# design.net
KiCad netlist of a schematic drawn in Altium Designer
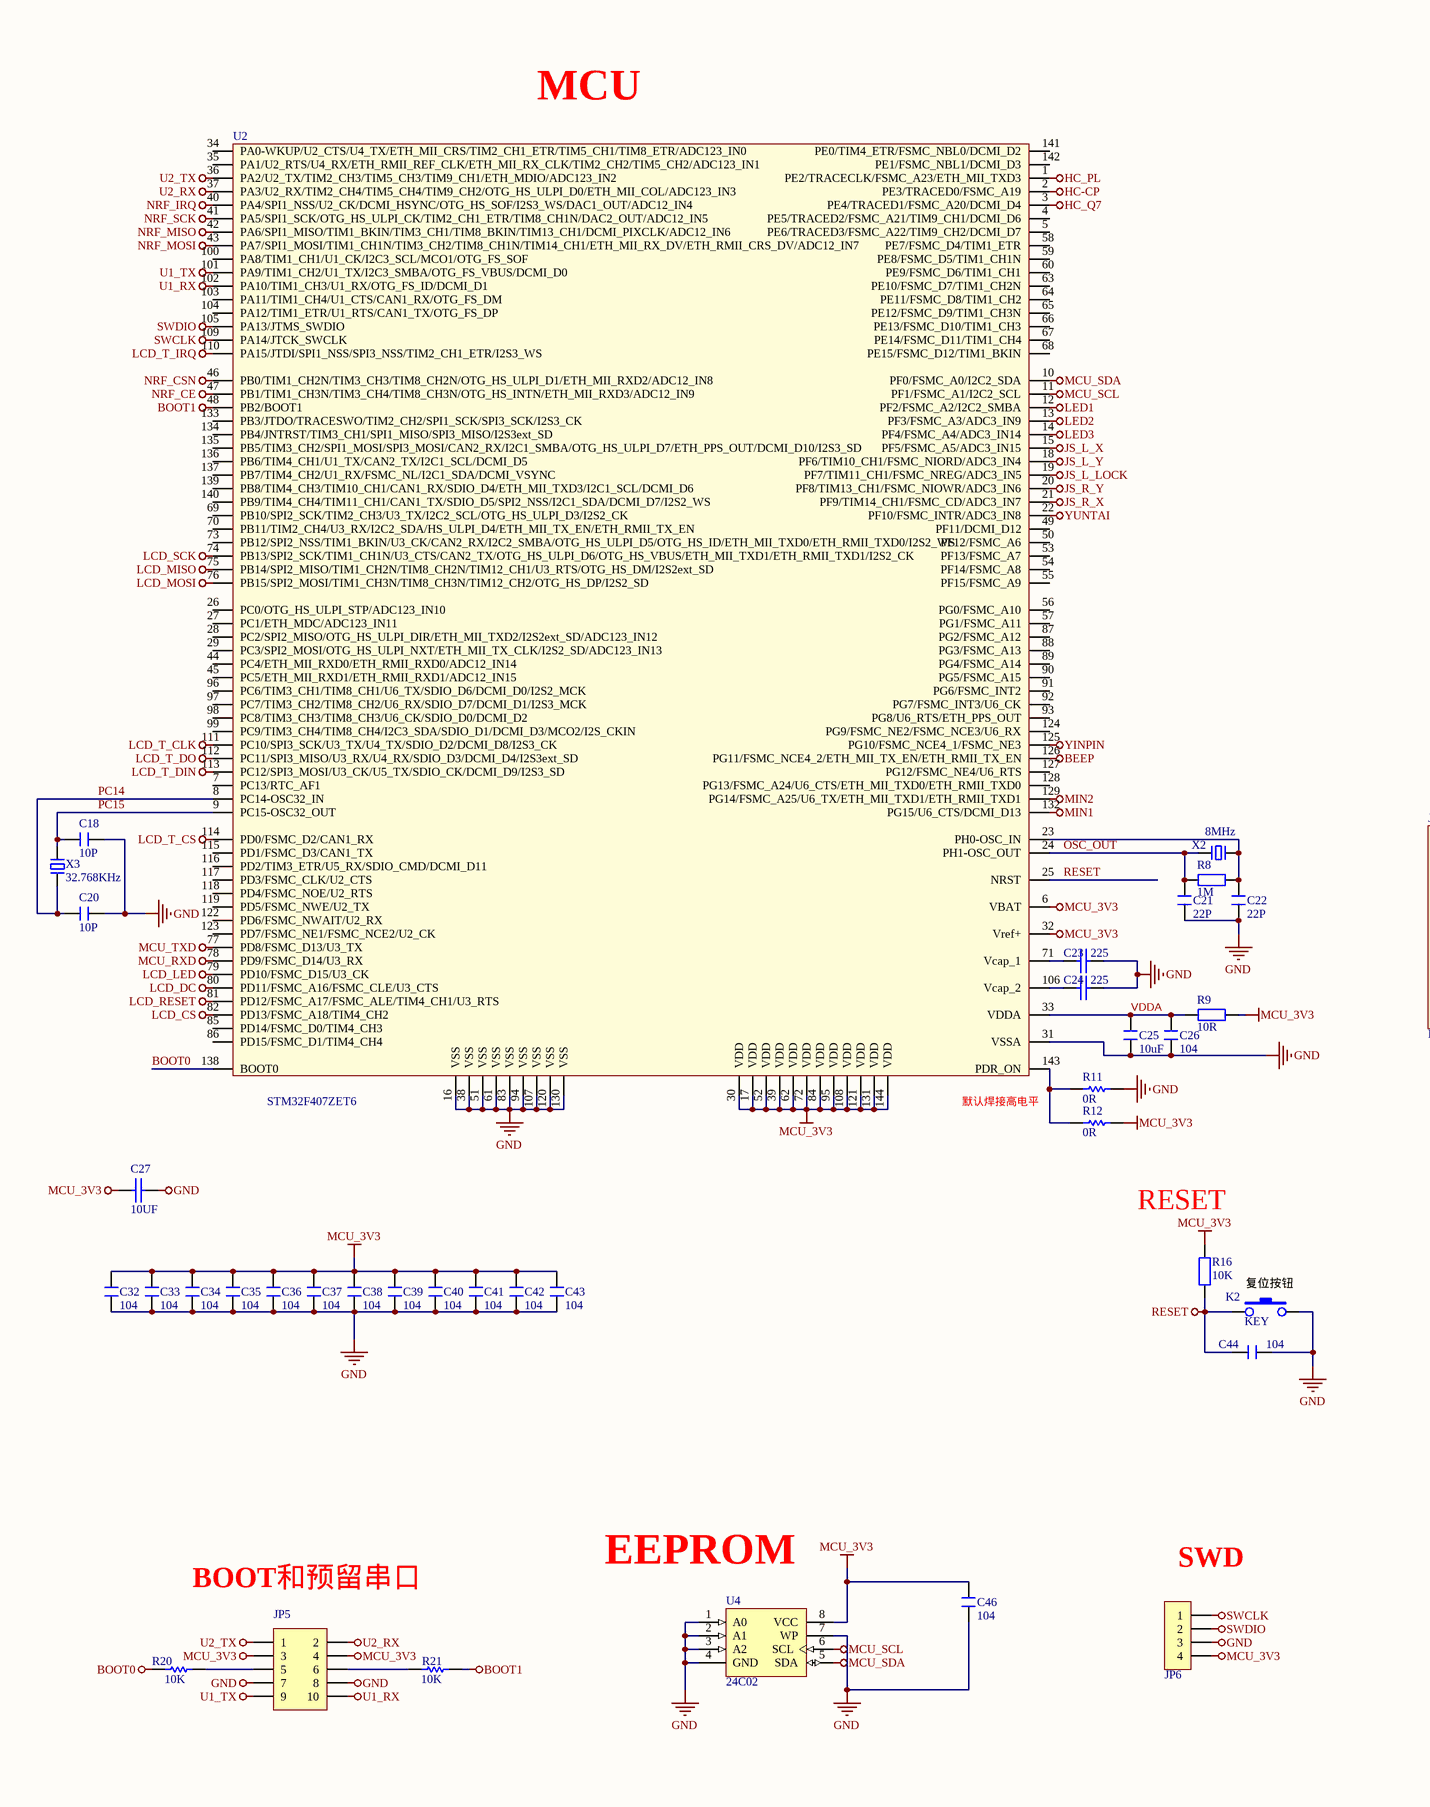
[diagram p0: 遥控器主板.SchDoc, left]
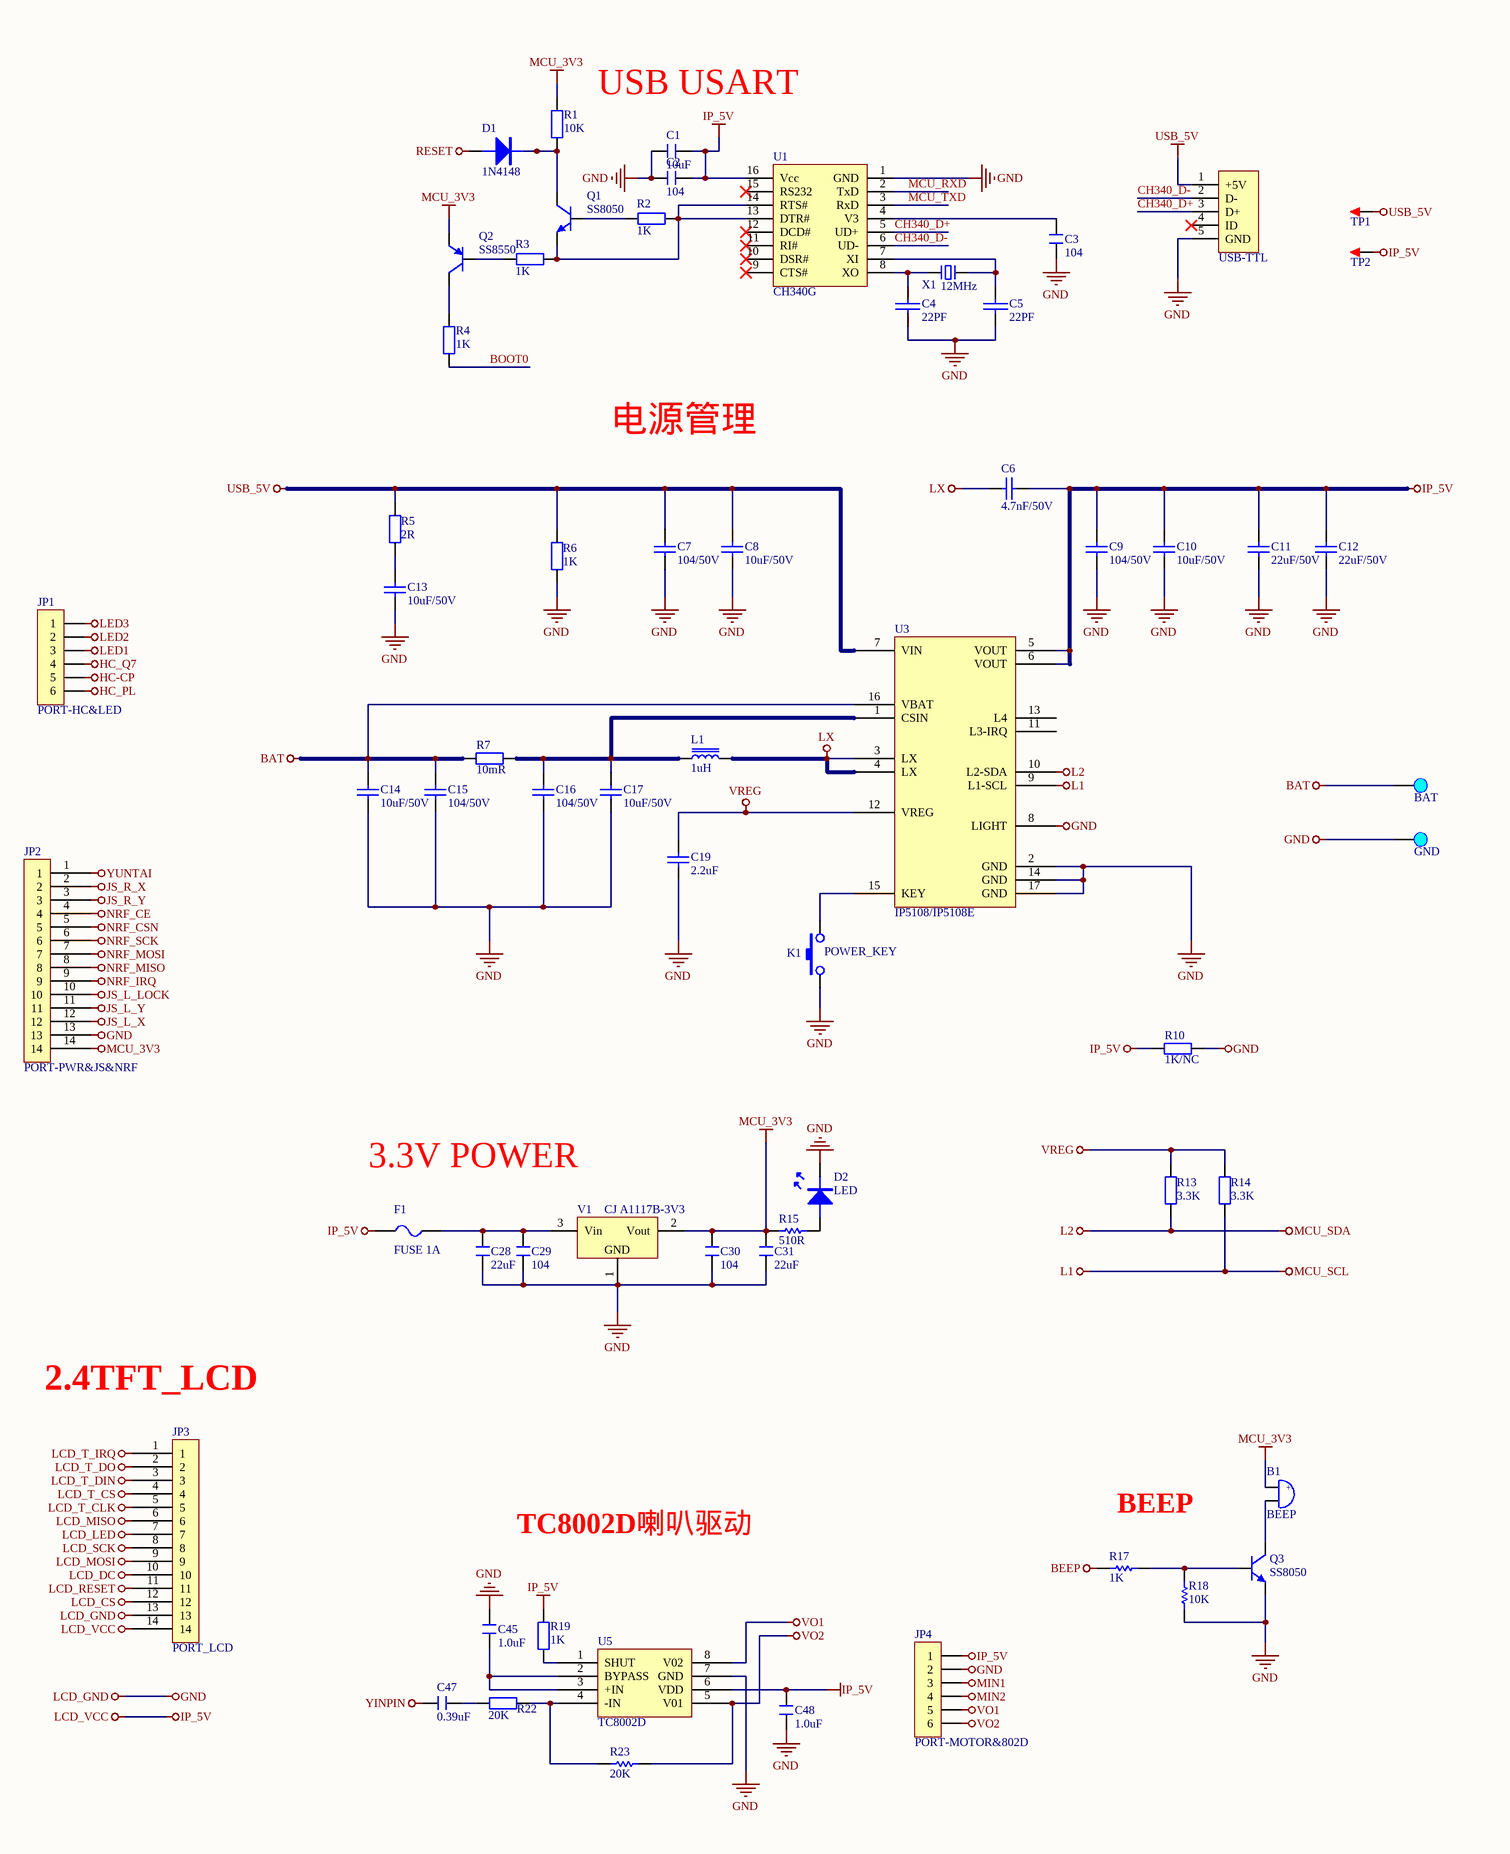
[diagram p1: 遥控器主板.SchDoc, right]

(export (version "E")
  (design (tool "Eeschema 10.0.6"))
  (components
    (comp (ref "B1")
      (value "BEEP")
      (footprint "BEEP 7.6X12X7.5")
      (description "蜂鸣器")
      (libsource (lib "蜂鸣器") (part "BEEP"))
    )
    (comp (ref "C1")
      (value "10uF")
      (footprint "0603C")
      (description "无极性贴片电容")
      (fields (field (name "版权归属") "源创客"))
      (libsource (lib "STM32F407_CORE_BOARD") (part "C"))
    )
    (comp (ref "C2")
      (value "104")
      (footprint "0603C")
      (description "无极性贴片电容")
      (fields (field (name "版权归属") "源创客"))
      (libsource (lib "STM32F407_CORE_BOARD") (part "C"))
    )
    (comp (ref "C3")
      (value "104")
      (footprint "0603C")
      (description "无极性贴片电容")
      (fields (field (name "版权归属") "源创客"))
      (libsource (lib "STM32F407_CORE_BOARD") (part "C"))
    )
    (comp (ref "C4")
      (value "22PF")
      (footprint "0603C")
      (description "无极性电容")
      (libsource (lib "电容") (part "CAP"))
    )
    (comp (ref "C5")
      (value "22PF")
      (footprint "0603C")
      (description "无极性电容")
      (libsource (lib "电容") (part "CAP"))
    )
    (comp (ref "C6")
      (value "4.7nF")
      (footprint "0603C")
      (fields (field (name "_PARAMETER") "4.7nF/50V"))
      (libsource (lib "元件库") (part "Cap"))
    )
    (comp (ref "C7")
      (value "104")
      (footprint "0603C")
      (fields (field (name "_PARAMETER") "104/50V"))
      (libsource (lib "元件库") (part "Cap"))
    )
    (comp (ref "C8")
      (value "10uF")
      (footprint "0603C")
      (fields (field (name "_PARAMETER") "10uF/50V"))
      (libsource (lib "元件库") (part "Cap"))
    )
    (comp (ref "C9")
      (value "104")
      (footprint "0603C")
      (fields (field (name "_PARAMETER") "104/50V"))
      (libsource (lib "元件库") (part "Cap"))
    )
    (comp (ref "C10")
      (value "10uF")
      (footprint "0603C")
      (fields (field (name "_PARAMETER") "10uF/50V"))
      (libsource (lib "元件库") (part "Cap"))
    )
    (comp (ref "C11")
      (value "22uF")
      (footprint "0603C")
      (fields (field (name "_PARAMETER") "22uF/50V"))
      (libsource (lib "元件库") (part "Cap"))
    )
    (comp (ref "C12")
      (value "22uF")
      (footprint "0603C")
      (fields (field (name "_PARAMETER") "22uF/50V"))
      (libsource (lib "元件库") (part "Cap"))
    )
    (comp (ref "C13")
      (value "10uF")
      (footprint "0603C")
      (fields (field (name "_PARAMETER") "10uF/50V"))
      (libsource (lib "元件库") (part "Cap"))
    )
    (comp (ref "C14")
      (value "10uF")
      (footprint "0603C")
      (fields (field (name "_PARAMETER") "10uF/50V"))
      (libsource (lib "元件库") (part "Cap"))
    )
    (comp (ref "C15")
      (value "104")
      (footprint "0603C")
      (fields (field (name "_PARAMETER") "104/50V"))
      (libsource (lib "元件库") (part "Cap"))
    )
    (comp (ref "C16")
      (value "104")
      (footprint "0603C")
      (fields (field (name "_PARAMETER") "104/50V"))
      (libsource (lib "元件库") (part "Cap"))
    )
    (comp (ref "C17")
      (value "10uF")
      (footprint "0603C")
      (fields (field (name "_PARAMETER") "10uF/50V"))
      (libsource (lib "元件库") (part "Cap"))
    )
    (comp (ref "C18")
      (value "10P")
      (footprint "0603C")
      (description "无极性贴片电容")
      (fields (field (name "版权归属") "源创客"))
      (libsource (lib "STM32F407_CORE_BOARD") (part "C"))
    )
    (comp (ref "C19")
      (value "104")
      (footprint "0603C")
      (fields (field (name "_PARAMETER") "2.2uF"))
      (libsource (lib "元件库") (part "Cap"))
    )
    (comp (ref "C20")
      (value "10P")
      (footprint "0603C")
      (description "无极性贴片电容")
      (fields (field (name "版权归属") "源创客"))
      (libsource (lib "STM32F407_CORE_BOARD") (part "C"))
    )
    (comp (ref "C21")
      (value "22P")
      (footprint "0603C")
      (description "无极性贴片电容")
      (fields (field (name "版权归属") "源创客"))
      (libsource (lib "STM32F407_CORE_BOARD") (part "C"))
    )
    (comp (ref "C22")
      (value "22P")
      (footprint "0603C")
      (description "无极性贴片电容")
      (fields (field (name "版权归属") "源创客"))
      (libsource (lib "STM32F407_CORE_BOARD") (part "C"))
    )
    (comp (ref "C23")
      (value "225")
      (footprint "0603C")
      (description "无极性电容")
      (libsource (lib "电容") (part "CAP"))
    )
    (comp (ref "C24")
      (value "225")
      (footprint "0603C")
      (description "无极性电容")
      (libsource (lib "电容") (part "CAP"))
    )
    (comp (ref "C25")
      (value "10uF")
      (footprint "0603C")
      (description "无极性贴片电容")
      (fields (field (name "版权归属") "源创客"))
      (libsource (lib "STM32F407_CORE_BOARD") (part "C"))
    )
    (comp (ref "C26")
      (value "104")
      (footprint "0603C")
      (description "无极性贴片电容")
      (fields (field (name "版权归属") "源创客"))
      (libsource (lib "STM32F407_CORE_BOARD") (part "C"))
    )
    (comp (ref "C27")
      (value "10UF")
      (footprint "0603C")
      (description "无极性电容")
      (libsource (lib "电容") (part "CAP"))
    )
    (comp (ref "C28")
      (value "22uF")
      (footprint "0603C")
      (description "无极性贴片电容")
      (fields (field (name "版权归属") "源创客"))
      (libsource (lib "STM32F407_CORE_BOARD") (part "C"))
    )
    (comp (ref "C29")
      (value "104")
      (footprint "0603C")
      (description "无极性贴片电容")
      (fields (field (name "版权归属") "源创客"))
      (libsource (lib "STM32F407_CORE_BOARD") (part "C"))
    )
    (comp (ref "C30")
      (value "104")
      (footprint "0603C")
      (description "无极性贴片电容")
      (fields (field (name "版权归属") "源创客"))
      (libsource (lib "STM32F407_CORE_BOARD") (part "C"))
    )
    (comp (ref "C31")
      (value "22uF")
      (footprint "0603C")
      (description "无极性贴片电容")
      (fields (field (name "版权归属") "源创客"))
      (libsource (lib "STM32F407_CORE_BOARD") (part "C"))
    )
    (comp (ref "C32")
      (value "104")
      (footprint "0603C")
      (description "无极性贴片电容")
      (fields (field (name "版权归属") "源创客"))
      (libsource (lib "STM32F407_CORE_BOARD") (part "C"))
    )
    (comp (ref "C33")
      (value "104")
      (footprint "0603C")
      (description "无极性贴片电容")
      (fields (field (name "版权归属") "源创客"))
      (libsource (lib "STM32F407_CORE_BOARD") (part "C"))
    )
    (comp (ref "C34")
      (value "104")
      (footprint "0603C")
      (description "无极性贴片电容")
      (fields (field (name "版权归属") "源创客"))
      (libsource (lib "STM32F407_CORE_BOARD") (part "C"))
    )
    (comp (ref "C35")
      (value "104")
      (footprint "0603C")
      (description "无极性贴片电容")
      (fields (field (name "版权归属") "源创客"))
      (libsource (lib "STM32F407_CORE_BOARD") (part "C"))
    )
    (comp (ref "C36")
      (value "104")
      (footprint "0603C")
      (description "无极性贴片电容")
      (fields (field (name "版权归属") "源创客"))
      (libsource (lib "STM32F407_CORE_BOARD") (part "C"))
    )
    (comp (ref "C37")
      (value "104")
      (footprint "0603C")
      (description "无极性贴片电容")
      (fields (field (name "版权归属") "源创客"))
      (libsource (lib "STM32F407_CORE_BOARD") (part "C"))
    )
    (comp (ref "C38")
      (value "104")
      (footprint "0603C")
      (description "无极性贴片电容")
      (fields (field (name "版权归属") "源创客"))
      (libsource (lib "STM32F407_CORE_BOARD") (part "C"))
    )
    (comp (ref "C39")
      (value "104")
      (footprint "0603C")
      (description "无极性贴片电容")
      (fields (field (name "版权归属") "源创客"))
      (libsource (lib "STM32F407_CORE_BOARD") (part "C"))
    )
    (comp (ref "C40")
      (value "104")
      (footprint "0603C")
      (description "无极性贴片电容")
      (fields (field (name "版权归属") "源创客"))
      (libsource (lib "STM32F407_CORE_BOARD") (part "C"))
    )
    (comp (ref "C41")
      (value "104")
      (footprint "0603C")
      (description "无极性贴片电容")
      (fields (field (name "版权归属") "源创客"))
      (libsource (lib "STM32F407_CORE_BOARD") (part "C"))
    )
    (comp (ref "C42")
      (value "104")
      (footprint "0603C")
      (description "无极性贴片电容")
      (fields (field (name "版权归属") "源创客"))
      (libsource (lib "STM32F407_CORE_BOARD") (part "C"))
    )
    (comp (ref "C43")
      (value "104")
      (footprint "0603C")
      (description "无极性贴片电容")
      (fields (field (name "版权归属") "源创客"))
      (libsource (lib "STM32F407_CORE_BOARD") (part "C"))
    )
    (comp (ref "C44")
      (value "104")
      (footprint "0603C")
      (description "无极性贴片电容")
      (fields (field (name "版权归属") "源创客"))
      (libsource (lib "STM32F407_CORE_BOARD") (part "C"))
    )
    (comp (ref "C45")
      (value "1.0uF")
      (footprint "0603C")
      (description "无极性贴片电容")
      (fields (field (name "版权归属") "源创客"))
      (libsource (lib "STM32F407_CORE_BOARD") (part "C"))
    )
    (comp (ref "C46")
      (value "104")
      (footprint "0603C")
      (description "无极性贴片电容")
      (fields (field (name "版权归属") "源创客"))
      (libsource (lib "STM32F407_CORE_BOARD") (part "C"))
    )
    (comp (ref "C47")
      (value "0.39uF")
      (footprint "0603C")
      (description "无极性贴片电容")
      (fields (field (name "版权归属") "源创客"))
      (libsource (lib "STM32F407_CORE_BOARD") (part "C"))
    )
    (comp (ref "C48")
      (value "1.0uF")
      (footprint "0603C")
      (description "无极性贴片电容")
      (fields (field (name "版权归属") "源创客"))
      (libsource (lib "STM32F407_CORE_BOARD") (part "C"))
    )
    (comp (ref "D1")
      (value "1N4148")
      (footprint "SOD-323")
      (description "普通二极管")
      (libsource (lib "二极管") (part "DIODE"))
    )
    (comp (ref "D2") (value "LED") (footprint "LED-0603G") (libsource (lib "LED") (part "LED")))
    (comp (ref "F1")
      (value "FUSE 1A")
      (footprint "FU 0805")
      (description "贴片保险丝")
      (fields (field (name "版权归属") "源创客"))
      (libsource (lib "STM32F407_CORE_BOARD") (part "FU"))
    )
    (comp (ref "JP1")
      (value "PORT-HC&LED")
      (footprint "SH1.0 S-W-6P")
      (description "6P接插件")
      (fields (field (name "版权归属") "源创客"))
      (libsource (lib "ATKF405 V1.1") (part "Header 6"))
    )
    (comp (ref "JP2")
      (value "PORT-PWR&JS&NRF")
      (footprint "Headr14")
      (description "卧贴 14PIN 1.25mm")
      (libsource (lib "") (part "HEADER 14_1"))
    )
    (comp (ref "JP3")
      (value "PORT_LCD")
      (footprint "Headr14")
      (description "卧贴 14PIN 1.25mm")
      (libsource (lib "遥控器主板") (part "HEADER 14"))
    )
    (comp (ref "JP4")
      (value "PORT-MOTOR&802D")
      (footprint "SH1.0 S-W-6P")
      (description "6P接插件")
      (fields (field (name "版权归属") "源创客"))
      (libsource (lib "ATKF405 V1.1") (part "Header 6"))
    )
    (comp (ref "JP5")
      (value "Header 5X2")
      (footprint "HDR2.54-LI-2x5P")
      (description "5*2P接插件")
      (fields (field (name "版权归属") "源创客"))
      (libsource (lib "STM32F407_CORE_BOARD") (part "Header 5X2"))
    )
    (comp (ref "JP6")
      (value "SWD")
      (footprint "XH2.54-WI-4P")
      (description "4P接插件")
      (fields (field (name "版权归属") "源创客"))
      (libsource (lib "STM32F407_CORE_BOARD") (part "Header 4"))
    )
    (comp (ref "K1") (value "POWER_KEY") (footprint "SMD-3X6X2.5") (libsource (lib "轻触开关") (part "KEY")))
    (comp (ref "K2") (value "KEY") (footprint "SMD-3X6X2.5") (libsource (lib "轻触开关") (part "KEY")))
    (comp (ref "L1")
      (value "1uH")
      (footprint "CD54")
      (fields (field (name "_VALUE") "1uH"))
      (libsource (lib "元件库") (part "Inductor Iron 2"))
    )
    (comp (ref "Pad1")
      (value "BAT")
      (footprint "TEST PAD 1.8")
      (fields (field (name "_REMARKS") "BAT"))
      (libsource (lib "元件库") (part "Pad"))
    )
    (comp (ref "Pad2")
      (value "GND")
      (footprint "TEST PAD 1.8")
      (fields (field (name "_REMARKS") "GND"))
      (libsource (lib "元件库") (part "Pad"))
    )
    (comp (ref "Q1")
      (value "SS8050")
      (footprint "SOT23-3L")
      (description "高频放大-NPN型")
      (fields (field (name "版权归属") "源创客"))
      (libsource (lib "STM32F407_CORE_BOARD") (part "8050-SMD"))
    )
    (comp (ref "Q2")
      (value "SS8550")
      (footprint "SOT23-3L")
      (description "高频放大-PNP型")
      (fields (field (name "版权归属") "源创客"))
      (libsource (lib "STM32F407_CORE_BOARD") (part "8550-SMD"))
    )
    (comp (ref "Q3")
      (value "SS8050")
      (footprint "SOT23-3L")
      (description "高频放大-NPN型")
      (fields (field (name "版权归属") "源创客"))
      (libsource (lib "ATKF405 V1.1") (part "8050-SMD"))
    )
    (comp (ref "R1")
      (value "10K")
      (footprint "0805R")
      (description "贴片电阻")
      (fields (field (name "版权归属") "源创客"))
      (libsource (lib "STM32F407_CORE_BOARD") (part "R"))
    )
    (comp (ref "R2")
      (value "1K")
      (footprint "0805R")
      (description "贴片电阻")
      (fields (field (name "版权归属") "源创客"))
      (libsource (lib "STM32F407_CORE_BOARD") (part "R"))
    )
    (comp (ref "R3")
      (value "1K")
      (footprint "0805R")
      (description "贴片电阻")
      (fields (field (name "版权归属") "源创客"))
      (libsource (lib "STM32F407_CORE_BOARD") (part "R"))
    )
    (comp (ref "R4")
      (value "1K")
      (footprint "0805R")
      (description "贴片电阻")
      (fields (field (name "版权归属") "源创客"))
      (libsource (lib "STM32F407_CORE_BOARD") (part "R"))
    )
    (comp (ref "R5")
      (value "2R")
      (footprint "0805R")
      (fields (field (name "_VALUE") "2R"))
      (libsource (lib "") (part "Res_1"))
    )
    (comp (ref "R6")
      (value "1K")
      (footprint "0805R")
      (fields (field (name "_VALUE") "1K"))
      (libsource (lib "") (part "Res_1"))
    )
    (comp (ref "R7")
      (value "10mR")
      (footprint "2512R")
      (fields (field (name "_VALUE") "10mR"))
      (libsource (lib "元件库") (part "Res"))
    )
    (comp (ref "R8")
      (value "1M")
      (footprint "0805R")
      (description "贴片电阻")
      (fields (field (name "版权归属") "源创客"))
      (libsource (lib "STM32F407_CORE_BOARD") (part "R"))
    )
    (comp (ref "R9")
      (value "10R")
      (footprint "0805R")
      (description "贴片电阻")
      (fields (field (name "版权归属") "源创客"))
      (libsource (lib "STM32F407_CORE_BOARD") (part "R"))
    )
    (comp (ref "R10")
      (value "1K/NC")
      (footprint "0805R")
      (fields (field (name "_VALUE") "1K/NC"))
      (libsource (lib "元件库") (part "Res"))
    )
    (comp (ref "R11") (value "0R") (footprint "0805R") (libsource (lib "电阻") (part "RES")))
    (comp (ref "R12") (value "0R") (footprint "0805R") (libsource (lib "电阻") (part "RES")))
    (comp (ref "R13")
      (value "3.3K")
      (footprint "0805R")
      (fields (field (name "_VALUE") "3.3K"))
      (libsource (lib "") (part "Res_2"))
    )
    (comp (ref "R14")
      (value "3.3K")
      (footprint "0805R")
      (fields (field (name "_VALUE") "3.3K"))
      (libsource (lib "") (part "Res_2"))
    )
    (comp (ref "R15") (value "510R") (footprint "0805R") (libsource (lib "电阻") (part "RES")))
    (comp (ref "R16")
      (value "10K")
      (footprint "0805R")
      (description "贴片电阻")
      (fields (field (name "版权归属") "源创客"))
      (libsource (lib "STM32F407_CORE_BOARD") (part "R"))
    )
    (comp (ref "R17") (value "1K") (footprint "0805R") (libsource (lib "电阻") (part "RES")))
    (comp (ref "R18") (value "10K") (footprint "0805R") (libsource (lib "电阻") (part "RES")))
    (comp (ref "R19")
      (value "1K")
      (footprint "0805R")
      (description "贴片电阻")
      (fields (field (name "版权归属") "源创客"))
      (libsource (lib "STM32F407_CORE_BOARD") (part "R"))
    )
    (comp (ref "R20") (value "10K") (footprint "0805R") (libsource (lib "电阻") (part "RES")))
    (comp (ref "R21") (value "10K") (footprint "0805R") (libsource (lib "电阻") (part "RES")))
    (comp (ref "R22")
      (value "20K")
      (footprint "0805R")
      (description "贴片电阻")
      (fields (field (name "版权归属") "源创客"))
      (libsource (lib "STM32F407_CORE_BOARD") (part "R"))
    )
    (comp (ref "R23") (value "20K") (footprint "0805R") (libsource (lib "电阻") (part "RES")))
    (comp (ref "TP1")
      (value "TEST")
      (footprint "TEST PAD 1.8")
      (description "测试点")
      (fields (field (name "版权归属") "源创客"))
      (libsource (lib "ATKF405 V1.1") (part "TEST"))
    )
    (comp (ref "TP2")
      (value "TEST")
      (footprint "TEST PAD 1.8")
      (description "测试点")
      (fields (field (name "版权归属") "源创客"))
      (libsource (lib "ATKF405 V1.1") (part "TEST"))
    )
    (comp (ref "U1")
      (value "CH340G")
      (footprint "SOP16_L")
      (description "串口转USB")
      (fields (field (name "版权归属") "源创客"))
      (libsource (lib "STM32F407_CORE_BOARD") (part "CH340G"))
    )
    (comp (ref "U2")
      (value "STM32F407ZET6")
      (footprint "LQFP144 20X20_M")
      (libsource (lib "STM32F407_CORE_BOARD") (part "STM32F407ZET6"))
    )
    (comp (ref "U3")
      (value "IP5108/IP5108E")
      (footprint "SOP16_PWR")
      (description "2A/1A Charger SoC")
      (libsource (lib "xSchlib") (part "IP5108/IP5108E"))
    )
    (comp (ref "U4")
      (value "24C02")
      (footprint "SOP8_L")
      (description "外置EEPROM")
      (fields (field (name "版权归属") "源创客"))
      (libsource (lib "STM32F407_CORE_BOARD") (part "24Cxx"))
    )
    (comp (ref "U5")
      (value "TC8002D")
      (footprint "SOP8_L")
      (description "SOP_8功放IC")
      (libsource (lib "遥控器主板") (part "TC8002D"))
    )
    (comp (ref "USB1")
      (value "USB-TTL")
      (footprint "USB-MINI-A")
      (description "微型USB母座")
      (fields (field (name "版权归属") "源创客"))
      (libsource (lib "STM32F407_CORE_BOARD") (part "USB-5P"))
    )
    (comp (ref "V1")
      (value "CJ A1117B-3V3")
      (footprint "SOT89_L")
      (description "三端稳压芯片")
      (fields (field (name "版权归属") "源创客"))
      (libsource (lib "STM32F407_CORE_BOARD") (part "AMS1117"))
    )
    (comp (ref "X1")
      (value "12MHz")
      (footprint "OSC HC-49S")
      (description "2脚无源脚晶振")
      (libsource (lib "晶振") (part "XTAL-2P"))
    )
    (comp (ref "X2")
      (value "8MHz")
      (footprint "OSC HC-49S")
      (description "2脚无源脚晶振")
      (fields (field (name "版权归属") "源创客"))
      (libsource (lib "STM32F407_CORE_BOARD") (part "XTAL-2P"))
    )
    (comp (ref "X3")
      (value "32.768KHz")
      (footprint "OSC HC-49S")
      (description "2脚无源脚晶振")
      (fields (field (name "版权归属") "源创客"))
      (libsource (lib "STM32F407_CORE_BOARD") (part "XTAL-2P"))
    )
  )
  (nets
    (net (code "2") (name "/CH340_D+") (class "Default")
      (node (ref "U1") (pin "5") (pinfunction "UD+_5") (pintype "passive"))
      (node (ref "USB1") (pin "3") (pinfunction "D+_3") (pintype "passive"))
    )
    (net (code "3") (name "/CH340_D-") (class "Default")
      (node (ref "U1") (pin "6") (pinfunction "UD-_6") (pintype "passive"))
      (node (ref "USB1") (pin "2") (pinfunction "D-_2") (pintype "passive"))
    )
    (net (code "4") (name "/OSC_OUT") (class "Default")
      (node (ref "C21") (pin "2") (pinfunction "2_2") (pintype "passive"))
      (node (ref "R8") (pin "1") (pinfunction "1_1") (pintype "passive"))
      (node (ref "U2") (pin "24") (pinfunction "PH1-OSC_OUT_24") (pintype "passive"))
      (node (ref "X2") (pin "2") (pinfunction "2_2") (pintype "passive"))
    )
    (net (code "5") (name "/PC14") (class "Default")
      (node (ref "C20") (pin "1") (pinfunction "1_1") (pintype "passive"))
      (node (ref "U2") (pin "8") (pinfunction "PC14-OSC32_IN_8") (pintype "passive"))
      (node (ref "X3") (pin "1") (pinfunction "1_1") (pintype "passive"))
    )
    (net (code "6") (name "/PC15") (class "Default")
      (node (ref "C18") (pin "1") (pinfunction "1_1") (pintype "passive"))
      (node (ref "U2") (pin "9") (pinfunction "PC15-OSC32_OUT_9") (pintype "passive"))
      (node (ref "X3") (pin "2") (pinfunction "2_2") (pintype "passive"))
    )
    (net (code "7") (name "/VDDA") (class "Default")
      (node (ref "C25") (pin "2") (pinfunction "2_2") (pintype "passive"))
      (node (ref "C26") (pin "2") (pinfunction "2_2") (pintype "passive"))
      (node (ref "R9") (pin "1") (pinfunction "1_1") (pintype "passive"))
      (node (ref "U2") (pin "33") (pinfunction "VDDA_33") (pintype "passive"))
    )
    (net (code "8") (name "BAT") (class "Default")
      (node (ref "C14") (pin "2") (pinfunction "2_2") (pintype "passive"))
      (node (ref "C15") (pin "2") (pinfunction "2_2") (pintype "passive"))
      (node (ref "Pad1") (pin "1") (pinfunction "*_1") (pintype "passive"))
      (node (ref "R7") (pin "1") (pinfunction "1_1") (pintype "passive"))
      (node (ref "U3") (pin "16") (pinfunction "VBAT_16") (pintype "passive"))
    )
    (net (code "9") (name "BEEP") (class "Default")
      (node (ref "R17") (pin "1") (pinfunction "1_1") (pintype "passive"))
      (node (ref "U2") (pin "126") (pinfunction "PG11/FSMC_NCE4_2/ETH_MII_TX_EN/ETH_RMII_TX_EN_126") (pintype "passive"))
    )
    (net (code "10") (name "BOOT0") (class "Default")
      (node (ref "R20") (pin "1") (pinfunction "1_1") (pintype "passive"))
      (node (ref "R4") (pin "2") (pinfunction "2_2") (pintype "passive"))
      (node (ref "U2") (pin "138") (pinfunction "BOOT0_138") (pintype "passive"))
    )
    (net (code "11") (name "BOOT1") (class "Default")
      (node (ref "R21") (pin "2") (pinfunction "2_2") (pintype "passive"))
      (node (ref "U2") (pin "48") (pinfunction "PB2/BOOT1_48") (pintype "passive"))
    )
    (net (code "12") (name "GND") (class "Default")
      (node (ref "C1") (pin "1") (pinfunction "1_1") (pintype "passive"))
      (node (ref "C10") (pin "1") (pinfunction "1_1") (pintype "passive"))
      (node (ref "C11") (pin "1") (pinfunction "1_1") (pintype "passive"))
      (node (ref "C12") (pin "1") (pinfunction "1_1") (pintype "passive"))
      (node (ref "C13") (pin "1") (pinfunction "1_1") (pintype "passive"))
      (node (ref "C14") (pin "1") (pinfunction "1_1") (pintype "passive"))
      (node (ref "C15") (pin "1") (pinfunction "1_1") (pintype "passive"))
      (node (ref "C16") (pin "1") (pinfunction "1_1") (pintype "passive"))
      (node (ref "C17") (pin "1") (pinfunction "1_1") (pintype "passive"))
      (node (ref "C18") (pin "2") (pinfunction "2_2") (pintype "passive"))
      (node (ref "C19") (pin "1") (pinfunction "1_1") (pintype "passive"))
      (node (ref "C2") (pin "1") (pinfunction "1_1") (pintype "passive"))
      (node (ref "C20") (pin "2") (pinfunction "2_2") (pintype "passive"))
      (node (ref "C21") (pin "1") (pinfunction "1_1") (pintype "passive"))
      (node (ref "C22") (pin "1") (pinfunction "1_1") (pintype "passive"))
      (node (ref "C23") (pin "2") (pinfunction "2_2") (pintype "passive"))
      (node (ref "C24") (pin "2") (pinfunction "2_2") (pintype "passive"))
      (node (ref "C25") (pin "1") (pinfunction "1_1") (pintype "passive"))
      (node (ref "C26") (pin "1") (pinfunction "1_1") (pintype "passive"))
      (node (ref "C27") (pin "2") (pinfunction "2_2") (pintype "passive"))
      (node (ref "C28") (pin "1") (pinfunction "1_1") (pintype "passive"))
      (node (ref "C29") (pin "1") (pinfunction "1_1") (pintype "passive"))
      (node (ref "C3") (pin "1") (pinfunction "1_1") (pintype "passive"))
      (node (ref "C30") (pin "1") (pinfunction "1_1") (pintype "passive"))
      (node (ref "C31") (pin "1") (pinfunction "1_1") (pintype "passive"))
      (node (ref "C32") (pin "1") (pinfunction "1_1") (pintype "passive"))
      (node (ref "C33") (pin "1") (pinfunction "1_1") (pintype "passive"))
      (node (ref "C34") (pin "1") (pinfunction "1_1") (pintype "passive"))
      (node (ref "C35") (pin "1") (pinfunction "1_1") (pintype "passive"))
      (node (ref "C36") (pin "1") (pinfunction "1_1") (pintype "passive"))
      (node (ref "C37") (pin "1") (pinfunction "1_1") (pintype "passive"))
      (node (ref "C38") (pin "1") (pinfunction "1_1") (pintype "passive"))
      (node (ref "C39") (pin "1") (pinfunction "1_1") (pintype "passive"))
      (node (ref "C4") (pin "1") (pinfunction "1_1") (pintype "passive"))
      (node (ref "C40") (pin "1") (pinfunction "1_1") (pintype "passive"))
      (node (ref "C41") (pin "1") (pinfunction "1_1") (pintype "passive"))
      (node (ref "C42") (pin "1") (pinfunction "1_1") (pintype "passive"))
      (node (ref "C43") (pin "1") (pinfunction "1_1") (pintype "passive"))
      (node (ref "C44") (pin "1") (pinfunction "1_1") (pintype "passive"))
      (node (ref "C45") (pin "2") (pinfunction "2_2") (pintype "passive"))
      (node (ref "C46") (pin "1") (pinfunction "1_1") (pintype "passive"))
      (node (ref "C48") (pin "1") (pinfunction "1_1") (pintype "passive"))
      (node (ref "C5") (pin "1") (pinfunction "1_1") (pintype "passive"))
      (node (ref "C7") (pin "1") (pinfunction "1_1") (pintype "passive"))
      (node (ref "C8") (pin "1") (pinfunction "1_1") (pintype "passive"))
      (node (ref "C9") (pin "1") (pinfunction "1_1") (pintype "passive"))
      (node (ref "D2") (pin "K") (pinfunction "K_K") (pintype "passive"))
      (node (ref "JP2") (pin "13") (pinfunction "13_13") (pintype "passive"))
      (node (ref "JP3") (pin "13") (pinfunction "13_13") (pintype "passive"))
      (node (ref "JP4") (pin "2") (pinfunction "2_2") (pintype "passive"))
      (node (ref "JP5") (pin "7") (pinfunction "7_7") (pintype "passive"))
      (node (ref "JP5") (pin "8") (pinfunction "8_8") (pintype "passive"))
      (node (ref "JP6") (pin "3") (pinfunction "3_3") (pintype "passive"))
      (node (ref "K1") (pin "1") (pinfunction "1_1") (pintype "passive"))
      (node (ref "K2") (pin "3") (pinfunction "3_3") (pintype "passive"))
      (node (ref "Pad2") (pin "1") (pinfunction "*_1") (pintype "passive"))
      (node (ref "Q3") (pin "2") (pinfunction "E_2") (pintype "passive"))
      (node (ref "R10") (pin "2") (pinfunction "2_2") (pintype "passive"))
      (node (ref "R11") (pin "2") (pinfunction "2_2") (pintype "passive"))
      (node (ref "R18") (pin "1") (pinfunction "1_1") (pintype "passive"))
      (node (ref "R6") (pin "2") (pinfunction "2_2") (pintype "passive"))
      (node (ref "U1") (pin "1") (pinfunction "GND_1") (pintype "passive"))
      (node (ref "U2") (pin "107") (pinfunction "VSS_107") (pintype "passive"))
      (node (ref "U2") (pin "120") (pinfunction "VSS_120") (pintype "passive"))
      (node (ref "U2") (pin "130") (pinfunction "VSS_130") (pintype "passive"))
      (node (ref "U2") (pin "16") (pinfunction "VSS_16") (pintype "passive"))
      (node (ref "U2") (pin "31") (pinfunction "VSSA_31") (pintype "passive"))
      (node (ref "U2") (pin "38") (pinfunction "VSS_38") (pintype "passive"))
      (node (ref "U2") (pin "51") (pinfunction "VSS_51") (pintype "passive"))
      (node (ref "U2") (pin "61") (pinfunction "VSS_61") (pintype "passive"))
      (node (ref "U2") (pin "83") (pinfunction "VSS_83") (pintype "passive"))
      (node (ref "U2") (pin "94") (pinfunction "VSS_94") (pintype "passive"))
      (node (ref "U3") (pin "14") (pinfunction "GND_14") (pintype "passive"))
      (node (ref "U3") (pin "17") (pinfunction "GND_17") (pintype "passive"))
      (node (ref "U3") (pin "2") (pinfunction "GND_2") (pintype "passive"))
      (node (ref "U3") (pin "8") (pinfunction "LIGHT_8") (pintype "passive"))
      (node (ref "U4") (pin "1") (pinfunction "A0_1") (pintype "input"))
      (node (ref "U4") (pin "2") (pinfunction "A1_2") (pintype "input"))
      (node (ref "U4") (pin "3") (pinfunction "A2_3") (pintype "input"))
      (node (ref "U4") (pin "4") (pinfunction "GND_4") (pintype "passive"))
      (node (ref "U4") (pin "7") (pinfunction "WP_7") (pintype "passive"))
      (node (ref "U5") (pin "7") (pinfunction "GND_7") (pintype "passive"))
      (node (ref "USB1") (pin "5") (pinfunction "GND_5") (pintype "passive"))
      (node (ref "V1") (pin "1") (pinfunction "GND_1") (pintype "passive"))
    )
    (net (code "13") (name "HC-CP") (class "Default")
      (node (ref "JP1") (pin "5") (pinfunction "5_5") (pintype "passive"))
      (node (ref "U2") (pin "2") (pinfunction "PE3/TRACED0/FSMC_A19_2") (pintype "passive"))
    )
    (net (code "14") (name "HC_PL") (class "Default")
      (node (ref "JP1") (pin "6") (pinfunction "6_6") (pintype "passive"))
      (node (ref "U2") (pin "1") (pinfunction "PE2/TRACECLK/FSMC_A23/ETH_MII_TXD3_1") (pintype "passive"))
    )
    (net (code "15") (name "HC_Q7") (class "Default")
      (node (ref "JP1") (pin "4") (pinfunction "4_4") (pintype "passive"))
      (node (ref "U2") (pin "3") (pinfunction "PE4/TRACED1/FSMC_A20/DCMI_D4_3") (pintype "passive"))
    )
    (net (code "16") (name "IP_5V") (class "Default")
      (node (ref "C1") (pin "2") (pinfunction "2_2") (pintype "passive"))
      (node (ref "C10") (pin "2") (pinfunction "2_2") (pintype "passive"))
      (node (ref "C11") (pin "2") (pinfunction "2_2") (pintype "passive"))
      (node (ref "C12") (pin "2") (pinfunction "2_2") (pintype "passive"))
      (node (ref "C2") (pin "2") (pinfunction "2_2") (pintype "passive"))
      (node (ref "C48") (pin "2") (pinfunction "2_2") (pintype "passive"))
      (node (ref "C6") (pin "1") (pinfunction "1_1") (pintype "passive"))
      (node (ref "C9") (pin "2") (pinfunction "2_2") (pintype "passive"))
      (node (ref "F1") (pin "1") (pinfunction "1_1") (pintype "passive"))
      (node (ref "JP3") (pin "14") (pinfunction "14_14") (pintype "passive"))
      (node (ref "JP4") (pin "1") (pinfunction "1_1") (pintype "passive"))
      (node (ref "R10") (pin "1") (pinfunction "1_1") (pintype "passive"))
      (node (ref "R19") (pin "2") (pinfunction "2_2") (pintype "passive"))
      (node (ref "TP2") (pin "1") (pinfunction "1_1") (pintype "passive"))
      (node (ref "U1") (pin "16") (pinfunction "Vcc_16") (pintype "passive"))
      (node (ref "U3") (pin "5") (pinfunction "VOUT_5") (pintype "passive"))
      (node (ref "U3") (pin "6") (pinfunction "VOUT_6") (pintype "passive"))
      (node (ref "U5") (pin "6") (pinfunction "VDD_6") (pintype "passive"))
    )
    (net (code "17") (name "JS_L_LOCK") (class "Default")
      (node (ref "JP2") (pin "10") (pinfunction "10_10") (pintype "passive"))
      (node (ref "U2") (pin "19") (pinfunction "PF7/TIM11_CH1/FSMC_NREG/ADC3_IN5_19") (pintype "passive"))
    )
    (net (code "18") (name "JS_L_X") (class "Default")
      (node (ref "JP2") (pin "12") (pinfunction "12_12") (pintype "passive"))
      (node (ref "U2") (pin "15") (pinfunction "PF5/FSMC_A5/ADC3_IN15_15") (pintype "passive"))
    )
    (net (code "19") (name "JS_L_Y") (class "Default")
      (node (ref "JP2") (pin "11") (pinfunction "11_11") (pintype "passive"))
      (node (ref "U2") (pin "18") (pinfunction "PF6/TIM10_CH1/FSMC_NIORD/ADC3_IN4_18") (pintype "passive"))
    )
    (net (code "20") (name "JS_R_X") (class "Default")
      (node (ref "JP2") (pin "2") (pinfunction "2_2") (pintype "passive"))
      (node (ref "U2") (pin "21") (pinfunction "PF9/TIM14_CH1/FSMC_CD/ADC3_IN7_21") (pintype "passive"))
    )
    (net (code "21") (name "JS_R_Y") (class "Default")
      (node (ref "JP2") (pin "3") (pinfunction "3_3") (pintype "passive"))
      (node (ref "U2") (pin "20") (pinfunction "PF8/TIM13_CH1/FSMC_NIOWR/ADC3_IN6_20") (pintype "passive"))
    )
    (net (code "22") (name "L1") (class "Default")
      (node (ref "R14") (pin "1") (pinfunction "1_1") (pintype "passive"))
      (node (ref "U2") (pin "11") (pinfunction "PF1/FSMC_A1/I2C2_SCL_11") (pintype "passive"))
      (node (ref "U3") (pin "9") (pinfunction "L1-SCL_9") (pintype "passive"))
      (node (ref "U4") (pin "6") (pinfunction "SCL_6") (pintype "input"))
    )
    (net (code "23") (name "L2") (class "Default")
      (node (ref "R13") (pin "1") (pinfunction "1_1") (pintype "passive"))
      (node (ref "U2") (pin "10") (pinfunction "PF0/FSMC_A0/I2C2_SDA_10") (pintype "passive"))
      (node (ref "U3") (pin "10") (pinfunction "L2-SDA_10") (pintype "passive"))
      (node (ref "U4") (pin "5") (pinfunction "SDA_5") (pintype "bidirectional"))
    )
    (net (code "24") (name "LCD_CS") (class "Default")
      (node (ref "JP3") (pin "12") (pinfunction "12_12") (pintype "passive"))
      (node (ref "U2") (pin "82") (pinfunction "PD13/FSMC_A18/TIM4_CH2_82") (pintype "passive"))
    )
    (net (code "25") (name "LCD_DC") (class "Default")
      (node (ref "JP3") (pin "10") (pinfunction "10_10") (pintype "passive"))
      (node (ref "U2") (pin "80") (pinfunction "PD11/FSMC_A16/FSMC_CLE/U3_CTS_80") (pintype "passive"))
    )
    (net (code "26") (name "LCD_LED") (class "Default")
      (node (ref "JP3") (pin "7") (pinfunction "7_7") (pintype "passive"))
      (node (ref "U2") (pin "79") (pinfunction "PD10/FSMC_D15/U3_CK_79") (pintype "passive"))
    )
    (net (code "27") (name "LCD_MISO") (class "Default")
      (node (ref "JP3") (pin "6") (pinfunction "6_6") (pintype "passive"))
      (node (ref "U2") (pin "75") (pinfunction "PB14/SPI2_MISO/TIM1_CH2N/TIM8_CH2N/TIM12_CH1/U3_RTS/OTG_HS_DM/I2S2ext_SD_75") (pintype "passive"))
    )
    (net (code "28") (name "LCD_MOSI") (class "Default")
      (node (ref "JP3") (pin "9") (pinfunction "9_9") (pintype "passive"))
      (node (ref "U2") (pin "76") (pinfunction "PB15/SPI2_MOSI/TIM1_CH3N/TIM8_CH3N/TIM12_CH2/OTG_HS_DP/I2S2_SD_76") (pintype "passive"))
    )
    (net (code "29") (name "LCD_RESET") (class "Default")
      (node (ref "JP3") (pin "11") (pinfunction "11_11") (pintype "passive"))
      (node (ref "U2") (pin "81") (pinfunction "PD12/FSMC_A17/FSMC_ALE/TIM4_CH1/U3_RTS_81") (pintype "passive"))
    )
    (net (code "30") (name "LCD_SCK") (class "Default")
      (node (ref "JP3") (pin "8") (pinfunction "8_8") (pintype "passive"))
      (node (ref "U2") (pin "74") (pinfunction "PB13/SPI2_SCK/TIM1_CH1N/U3_CTS/CAN2_TX/OTG_HS_ULPI_D6/OTG_HS_VBUS/ETH_MII_TXD1/ETH_RMII_TXD1/I2S2_CK_74") (pintype "passive"))
    )
    (net (code "31") (name "LCD_T_CLK") (class "Default")
      (node (ref "JP3") (pin "5") (pinfunction "5_5") (pintype "passive"))
      (node (ref "U2") (pin "111") (pinfunction "PC10/SPI3_SCK/U3_TX/U4_TX/SDIO_D2/DCMI_D8/I2S3_CK_111") (pintype "passive"))
    )
    (net (code "32") (name "LCD_T_CS") (class "Default")
      (node (ref "JP3") (pin "4") (pinfunction "4_4") (pintype "passive"))
      (node (ref "U2") (pin "114") (pinfunction "PD0/FSMC_D2/CAN1_RX_114") (pintype "passive"))
    )
    (net (code "33") (name "LCD_T_DIN") (class "Default")
      (node (ref "JP3") (pin "3") (pinfunction "3_3") (pintype "passive"))
      (node (ref "U2") (pin "113") (pinfunction "PC12/SPI3_MOSI/U3_CK/U5_TX/SDIO_CK/DCMI_D9/I2S3_SD_113") (pintype "passive"))
    )
    (net (code "34") (name "LCD_T_DO") (class "Default")
      (node (ref "JP3") (pin "2") (pinfunction "2_2") (pintype "passive"))
      (node (ref "U2") (pin "112") (pinfunction "PC11/SPI3_MISO/U3_RX/U4_RX/SDIO_D3/DCMI_D4/I2S3ext_SD_112") (pintype "passive"))
    )
    (net (code "35") (name "LCD_T_IRQ") (class "Default")
      (node (ref "JP3") (pin "1") (pinfunction "1_1") (pintype "passive"))
      (node (ref "U2") (pin "110") (pinfunction "PA15/JTDI/SPI1_NSS/SPI3_NSS/TIM2_CH1_ETR/I2S3_WS_110") (pintype "passive"))
    )
    (net (code "36") (name "LED1") (class "Default")
      (node (ref "JP1") (pin "3") (pinfunction "3_3") (pintype "passive"))
      (node (ref "U2") (pin "12") (pinfunction "PF2/FSMC_A2/I2C2_SMBA_12") (pintype "passive"))
    )
    (net (code "37") (name "LED2") (class "Default")
      (node (ref "JP1") (pin "2") (pinfunction "2_2") (pintype "passive"))
      (node (ref "U2") (pin "13") (pinfunction "PF3/FSMC_A3/ADC3_IN9_13") (pintype "passive"))
    )
    (net (code "38") (name "LED3") (class "Default")
      (node (ref "JP1") (pin "1") (pinfunction "1_1") (pintype "passive"))
      (node (ref "U2") (pin "14") (pinfunction "PF4/FSMC_A4/ADC3_IN14_14") (pintype "passive"))
    )
    (net (code "39") (name "LX") (class "Default")
      (node (ref "C6") (pin "2") (pinfunction "2_2") (pintype "passive"))
      (node (ref "L1") (pin "2") (pinfunction "2_2") (pintype "passive"))
      (node (ref "U3") (pin "3") (pinfunction "LX_3") (pintype "passive"))
      (node (ref "U3") (pin "4") (pinfunction "LX_4") (pintype "passive"))
    )
    (net (code "40") (name "MCU_3V3") (class "Default")
      (node (ref "B1") (pin "1") (pinfunction "1_1") (pintype "passive"))
      (node (ref "C27") (pin "1") (pinfunction "1_1") (pintype "passive"))
      (node (ref "C30") (pin "2") (pinfunction "2_2") (pintype "passive"))
      (node (ref "C31") (pin "2") (pinfunction "2_2") (pintype "passive"))
      (node (ref "C32") (pin "2") (pinfunction "2_2") (pintype "passive"))
      (node (ref "C33") (pin "2") (pinfunction "2_2") (pintype "passive"))
      (node (ref "C34") (pin "2") (pinfunction "2_2") (pintype "passive"))
      (node (ref "C35") (pin "2") (pinfunction "2_2") (pintype "passive"))
      (node (ref "C36") (pin "2") (pinfunction "2_2") (pintype "passive"))
      (node (ref "C37") (pin "2") (pinfunction "2_2") (pintype "passive"))
      (node (ref "C38") (pin "2") (pinfunction "2_2") (pintype "passive"))
      (node (ref "C39") (pin "2") (pinfunction "2_2") (pintype "passive"))
      (node (ref "C40") (pin "2") (pinfunction "2_2") (pintype "passive"))
      (node (ref "C41") (pin "2") (pinfunction "2_2") (pintype "passive"))
      (node (ref "C42") (pin "2") (pinfunction "2_2") (pintype "passive"))
      (node (ref "C43") (pin "2") (pinfunction "2_2") (pintype "passive"))
      (node (ref "C46") (pin "2") (pinfunction "2_2") (pintype "passive"))
      (node (ref "JP2") (pin "14") (pinfunction "14_14") (pintype "passive"))
      (node (ref "JP5") (pin "3") (pinfunction "3_3") (pintype "passive"))
      (node (ref "JP5") (pin "4") (pinfunction "4_4") (pintype "passive"))
      (node (ref "JP6") (pin "4") (pinfunction "4_4") (pintype "passive"))
      (node (ref "Q2") (pin "2") (pinfunction "E_2") (pintype "passive"))
      (node (ref "R1") (pin "2") (pinfunction "2_2") (pintype "passive"))
      (node (ref "R12") (pin "2") (pinfunction "2_2") (pintype "passive"))
      (node (ref "R15") (pin "2") (pinfunction "2_2") (pintype "passive"))
      (node (ref "R16") (pin "2") (pinfunction "2_2") (pintype "passive"))
      (node (ref "R9") (pin "2") (pinfunction "2_2") (pintype "passive"))
      (node (ref "U2") (pin "108") (pinfunction "VDD_108") (pintype "passive"))
      (node (ref "U2") (pin "121") (pinfunction "VDD_121") (pintype "passive"))
      (node (ref "U2") (pin "131") (pinfunction "VDD_131") (pintype "passive"))
      (node (ref "U2") (pin "144") (pinfunction "VDD_144") (pintype "passive"))
      (node (ref "U2") (pin "17") (pinfunction "VDD_17") (pintype "passive"))
      (node (ref "U2") (pin "30") (pinfunction "VDD_30") (pintype "passive"))
      (node (ref "U2") (pin "32") (pinfunction "Vref+_32") (pintype "passive"))
      (node (ref "U2") (pin "39") (pinfunction "VDD_39") (pintype "passive"))
      (node (ref "U2") (pin "52") (pinfunction "VDD_52") (pintype "passive"))
      (node (ref "U2") (pin "6") (pinfunction "VBAT_6") (pintype "passive"))
      (node (ref "U2") (pin "62") (pinfunction "VDD_62") (pintype "passive"))
      (node (ref "U2") (pin "72") (pinfunction "VDD_72") (pintype "passive"))
      (node (ref "U2") (pin "84") (pinfunction "VDD_84") (pintype "passive"))
      (node (ref "U2") (pin "95") (pinfunction "VDD_95") (pintype "passive"))
      (node (ref "U4") (pin "8") (pinfunction "VCC_8") (pintype "power_in"))
      (node (ref "V1") (pin "2") (pinfunction "Vout_2") (pintype "passive"))
    )
    (net (code "41") (name "MCU_RXD") (class "Default")
      (node (ref "U1") (pin "2") (pinfunction "TxD_2") (pintype "passive"))
      (node (ref "U2") (pin "78") (pinfunction "PD9/FSMC_D14/U3_RX_78") (pintype "passive"))
    )
    (net (code "42") (name "MCU_TXD") (class "Default")
      (node (ref "U1") (pin "3") (pinfunction "RxD_3") (pintype "passive"))
      (node (ref "U2") (pin "77") (pinfunction "PD8/FSMC_D13/U3_TX_77") (pintype "passive"))
    )
    (net (code "43") (name "MIN1") (class "Default")
      (node (ref "JP4") (pin "3") (pinfunction "3_3") (pintype "passive"))
      (node (ref "U2") (pin "132") (pinfunction "PG15/U6_CTS/DCMI_D13_132") (pintype "passive"))
    )
    (net (code "44") (name "MIN2") (class "Default")
      (node (ref "JP4") (pin "4") (pinfunction "4_4") (pintype "passive"))
      (node (ref "U2") (pin "129") (pinfunction "PG14/FSMC_A25/U6_TX/ETH_MII_TXD1/ETH_RMII_TXD1_129") (pintype "passive"))
    )
    (net (code "45") (name "NRF_CE") (class "Default")
      (node (ref "JP2") (pin "4") (pinfunction "4_4") (pintype "passive"))
      (node (ref "U2") (pin "47") (pinfunction "PB1/TIM1_CH3N/TIM3_CH4/TIM8_CH3N/OTG_HS_INTN/ETH_MII_RXD3/ADC12_IN9_47") (pintype "passive"))
    )
    (net (code "46") (name "NRF_CSN") (class "Default")
      (node (ref "JP2") (pin "5") (pinfunction "5_5") (pintype "passive"))
      (node (ref "U2") (pin "46") (pinfunction "PB0/TIM1_CH2N/TIM3_CH3/TIM8_CH2N/OTG_HS_ULPI_D1/ETH_MII_RXD2/ADC12_IN8_46") (pintype "passive"))
    )
    (net (code "47") (name "NRF_IRQ") (class "Default")
      (node (ref "JP2") (pin "9") (pinfunction "9_9") (pintype "passive"))
      (node (ref "U2") (pin "40") (pinfunction "PA4/SPI1_NSS/U2_CK/DCMI_HSYNC/OTG_HS_SOF/I2S3_WS/DAC1_OUT/ADC12_IN4_40") (pintype "passive"))
    )
    (net (code "48") (name "NRF_MISO") (class "Default")
      (node (ref "JP2") (pin "8") (pinfunction "8_8") (pintype "passive"))
      (node (ref "U2") (pin "42") (pinfunction "PA6/SPI1_MISO/TIM1_BKIN/TIM3_CH1/TIM8_BKIN/TIM13_CH1/DCMI_PIXCLK/ADC12_IN6_42") (pintype "passive"))
    )
    (net (code "49") (name "NRF_MOSI") (class "Default")
      (node (ref "JP2") (pin "7") (pinfunction "7_7") (pintype "passive"))
      (node (ref "U2") (pin "43") (pinfunction "PA7/SPI1_MOSI/TIM1_CH1N/TIM3_CH2/TIM8_CH1N/TIM14_CH1/ETH_MII_RX_DV/ETH_RMII_CRS_DV/ADC12_IN7_43") (pintype "passive"))
    )
    (net (code "50") (name "NRF_SCK") (class "Default")
      (node (ref "JP2") (pin "6") (pinfunction "6_6") (pintype "passive"))
      (node (ref "U2") (pin "41") (pinfunction "PA5/SPI1_SCK/OTG_HS_ULPI_CK/TIM2_CH1_ETR/TIM8_CH1N/DAC2_OUT/ADC12_IN5_41") (pintype "passive"))
    )
    (net (code "51") (name "Net-(C13-Pad2)") (class "Default")
      (node (ref "C13") (pin "2") (pinfunction "2_2") (pintype "passive"))
      (node (ref "R5") (pin "2") (pinfunction "2_2") (pintype "passive"))
    )
    (net (code "52") (name "Net-(C47-Pad1)") (class "Default")
      (node (ref "C47") (pin "1") (pinfunction "1_1") (pintype "passive"))
      (node (ref "R22") (pin "1") (pinfunction "1_1") (pintype "passive"))
    )
    (net (code "53") (name "Net-(D2-PadA)") (class "Default")
      (node (ref "D2") (pin "A") (pinfunction "A_A") (pintype "passive"))
      (node (ref "R15") (pin "1") (pinfunction "1_1") (pintype "passive"))
    )
    (net (code "54") (name "Net-(JP5-Pad5)") (class "Default")
      (node (ref "JP5") (pin "5") (pinfunction "5_5") (pintype "passive"))
      (node (ref "R20") (pin "2") (pinfunction "2_2") (pintype "passive"))
    )
    (net (code "55") (name "Net-(JP5-Pad6)") (class "Default")
      (node (ref "JP5") (pin "6") (pinfunction "6_6") (pintype "passive"))
      (node (ref "R21") (pin "1") (pinfunction "1_1") (pintype "passive"))
    )
    (net (code "56") (name "Net-(Q1-B)") (class "Default")
      (node (ref "Q1") (pin "1") (pinfunction "B_1") (pintype "passive"))
      (node (ref "R2") (pin "2") (pinfunction "2_2") (pintype "passive"))
    )
    (net (code "57") (name "Net-(Q1-C)") (class "Default")
      (node (ref "D1") (pin "K") (pinfunction "K_K") (pintype "passive"))
      (node (ref "Q1") (pin "3") (pinfunction "C_3") (pintype "passive"))
      (node (ref "R1") (pin "1") (pinfunction "1_1") (pintype "passive"))
    )
    (net (code "58") (name "Net-(Q1-E)") (class "Default")
      (node (ref "Q1") (pin "2") (pinfunction "E_2") (pintype "passive"))
      (node (ref "R2") (pin "1") (pinfunction "1_1") (pintype "passive"))
      (node (ref "R3") (pin "1") (pinfunction "1_1") (pintype "passive"))
      (node (ref "U1") (pin "13") (pinfunction "DTR#_13") (pintype "passive"))
      (node (ref "U1") (pin "14") (pinfunction "RTS#_14") (pintype "passive"))
    )
    (net (code "59") (name "Net-(Q2-B)") (class "Default")
      (node (ref "Q2") (pin "1") (pinfunction "B_1") (pintype "passive"))
      (node (ref "R3") (pin "2") (pinfunction "2_2") (pintype "passive"))
    )
    (net (code "60") (name "Net-(Q2-C)") (class "Default")
      (node (ref "Q2") (pin "3") (pinfunction "C_3") (pintype "passive"))
      (node (ref "R4") (pin "1") (pinfunction "1_1") (pintype "passive"))
    )
    (net (code "61") (name "Net-(Q3-B)") (class "Default")
      (node (ref "Q3") (pin "1") (pinfunction "B_1") (pintype "passive"))
      (node (ref "R17") (pin "2") (pinfunction "2_2") (pintype "passive"))
      (node (ref "R18") (pin "2") (pinfunction "2_2") (pintype "passive"))
    )
    (net (code "62") (name "Net-(Q3-C)") (class "Default")
      (node (ref "B1") (pin "2") (pinfunction "2_2") (pintype "passive"))
      (node (ref "Q3") (pin "3") (pinfunction "C_3") (pintype "passive"))
    )
    (net (code "63") (name "Net-(U1-V3)") (class "Default")
      (node (ref "C3") (pin "2") (pinfunction "2_2") (pintype "passive"))
      (node (ref "U1") (pin "4") (pinfunction "V3_4") (pintype "passive"))
    )
    (net (code "64") (name "Net-(U1-XI)") (class "Default")
      (node (ref "C5") (pin "2") (pinfunction "2_2") (pintype "passive"))
      (node (ref "U1") (pin "7") (pinfunction "XI_7") (pintype "passive"))
      (node (ref "X1") (pin "2") (pinfunction "2_2") (pintype "passive"))
    )
    (net (code "65") (name "Net-(U1-XO)") (class "Default")
      (node (ref "C4") (pin "2") (pinfunction "2_2") (pintype "passive"))
      (node (ref "U1") (pin "8") (pinfunction "XO_8") (pintype "passive"))
      (node (ref "X1") (pin "1") (pinfunction "1_1") (pintype "passive"))
    )
    (net (code "66") (name "Net-(U2-PDR_ON)") (class "Default")
      (node (ref "R11") (pin "1") (pinfunction "1_1") (pintype "passive"))
      (node (ref "R12") (pin "1") (pinfunction "1_1") (pintype "passive"))
      (node (ref "U2") (pin "143") (pinfunction "PDR_ON_143") (pintype "passive"))
    )
    (net (code "67") (name "Net-(U2-PH0-OSC_IN)") (class "Default")
      (node (ref "C22") (pin "2") (pinfunction "2_2") (pintype "passive"))
      (node (ref "R8") (pin "2") (pinfunction "2_2") (pintype "passive"))
      (node (ref "U2") (pin "23") (pinfunction "PH0-OSC_IN_23") (pintype "passive"))
      (node (ref "X2") (pin "1") (pinfunction "1_1") (pintype "passive"))
    )
    (net (code "68") (name "Net-(U2-Vcap_1)") (class "Default")
      (node (ref "C23") (pin "1") (pinfunction "1_1") (pintype "passive"))
      (node (ref "U2") (pin "71") (pinfunction "Vcap_1_71") (pintype "passive"))
    )
    (net (code "69") (name "Net-(U2-Vcap_2)") (class "Default")
      (node (ref "C24") (pin "1") (pinfunction "1_1") (pintype "passive"))
      (node (ref "U2") (pin "106") (pinfunction "Vcap_2_106") (pintype "passive"))
    )
    (net (code "70") (name "Net-(U3-CSIN)") (class "Default")
      (node (ref "C16") (pin "2") (pinfunction "2_2") (pintype "passive"))
      (node (ref "C17") (pin "2") (pinfunction "2_2") (pintype "passive"))
      (node (ref "L1") (pin "1") (pinfunction "1_1") (pintype "passive"))
      (node (ref "R7") (pin "2") (pinfunction "2_2") (pintype "passive"))
      (node (ref "U3") (pin "1") (pinfunction "CSIN_1") (pintype "passive"))
    )
    (net (code "71") (name "Net-(U3-KEY)") (class "Default")
      (node (ref "K1") (pin "3") (pinfunction "3_3") (pintype "passive"))
      (node (ref "U3") (pin "15") (pinfunction "KEY_15") (pintype "passive"))
    )
    (net (code "72") (name "Net-(U5-+IN)") (class "Default")
      (node (ref "C45") (pin "1") (pinfunction "1_1") (pintype "passive"))
      (node (ref "U5") (pin "2") (pinfunction "BYPASS_2") (pintype "passive"))
      (node (ref "U5") (pin "3") (pinfunction "+IN_3") (pintype "passive"))
    )
    (net (code "73") (name "Net-(U5--IN)") (class "Default")
      (node (ref "R22") (pin "2") (pinfunction "2_2") (pintype "passive"))
      (node (ref "R23") (pin "1") (pinfunction "1_1") (pintype "passive"))
      (node (ref "U5") (pin "4") (pinfunction "-IN_4") (pintype "passive"))
    )
    (net (code "74") (name "Net-(U5-SHUT)") (class "Default")
      (node (ref "R19") (pin "1") (pinfunction "1_1") (pintype "passive"))
      (node (ref "U5") (pin "1") (pinfunction "SHUT_1") (pintype "passive"))
    )
    (net (code "75") (name "Net-(V1-Vin)") (class "Default")
      (node (ref "C28") (pin "2") (pinfunction "2_2") (pintype "passive"))
      (node (ref "C29") (pin "2") (pinfunction "2_2") (pintype "passive"))
      (node (ref "F1") (pin "2") (pinfunction "2_2") (pintype "passive"))
      (node (ref "V1") (pin "3") (pinfunction "Vin_3") (pintype "passive"))
    )
    (net (code "76") (name "RESET") (class "Default")
      (node (ref "C44") (pin "2") (pinfunction "2_2") (pintype "passive"))
      (node (ref "D1") (pin "A") (pinfunction "A_A") (pintype "passive"))
      (node (ref "K2") (pin "1") (pinfunction "1_1") (pintype "passive"))
      (node (ref "R16") (pin "1") (pinfunction "1_1") (pintype "passive"))
      (node (ref "U2") (pin "25") (pinfunction "NRST_25") (pintype "passive"))
    )
    (net (code "77") (name "SWCLK") (class "Default")
      (node (ref "JP6") (pin "1") (pinfunction "1_1") (pintype "passive"))
      (node (ref "U2") (pin "109") (pinfunction "PA14/JTCK_SWCLK_109") (pintype "passive"))
    )
    (net (code "78") (name "SWDIO") (class "Default")
      (node (ref "JP6") (pin "2") (pinfunction "2_2") (pintype "passive"))
      (node (ref "U2") (pin "105") (pinfunction "PA13/JTMS_SWDIO_105") (pintype "passive"))
    )
    (net (code "79") (name "U1_RX") (class "Default")
      (node (ref "JP5") (pin "10") (pinfunction "10_10") (pintype "passive"))
      (node (ref "U2") (pin "102") (pinfunction "PA10/TIM1_CH3/U1_RX/OTG_FS_ID/DCMI_D1_102") (pintype "passive"))
    )
    (net (code "80") (name "U1_TX") (class "Default")
      (node (ref "JP5") (pin "9") (pinfunction "9_9") (pintype "passive"))
      (node (ref "U2") (pin "101") (pinfunction "PA9/TIM1_CH2/U1_TX/I2C3_SMBA/OTG_FS_VBUS/DCMI_D0_101") (pintype "passive"))
    )
    (net (code "81") (name "U2_RX") (class "Default")
      (node (ref "JP5") (pin "2") (pinfunction "2_2") (pintype "passive"))
      (node (ref "U2") (pin "37") (pinfunction "PA3/U2_RX/TIM2_CH4/TIM5_CH4/TIM9_CH2/OTG_HS_ULPI_D0/ETH_MII_COL/ADC123_IN3_37") (pintype "passive"))
    )
    (net (code "82") (name "U2_TX") (class "Default")
      (node (ref "JP5") (pin "1") (pinfunction "1_1") (pintype "passive"))
      (node (ref "U2") (pin "36") (pinfunction "PA2/U2_TX/TIM2_CH3/TIM5_CH3/TIM9_CH1/ETH_MDIO/ADC123_IN2_36") (pintype "passive"))
    )
    (net (code "83") (name "USB_5V") (class "Default")
      (node (ref "C7") (pin "2") (pinfunction "2_2") (pintype "passive"))
      (node (ref "C8") (pin "2") (pinfunction "2_2") (pintype "passive"))
      (node (ref "R5") (pin "1") (pinfunction "1_1") (pintype "passive"))
      (node (ref "R6") (pin "1") (pinfunction "1_1") (pintype "passive"))
      (node (ref "TP1") (pin "1") (pinfunction "1_1") (pintype "passive"))
      (node (ref "U3") (pin "7") (pinfunction "VIN_7") (pintype "passive"))
      (node (ref "USB1") (pin "1") (pinfunction "+5V_1") (pintype "passive"))
    )
    (net (code "84") (name "VO1") (class "Default")
      (node (ref "JP4") (pin "5") (pinfunction "5_5") (pintype "passive"))
      (node (ref "U5") (pin "8") (pinfunction "V02_8") (pintype "passive"))
    )
    (net (code "85") (name "VO2") (class "Default")
      (node (ref "JP4") (pin "6") (pinfunction "6_6") (pintype "passive"))
      (node (ref "R23") (pin "2") (pinfunction "2_2") (pintype "passive"))
      (node (ref "U5") (pin "5") (pinfunction "V01_5") (pintype "passive"))
    )
    (net (code "86") (name "VREG") (class "Default")
      (node (ref "C19") (pin "2") (pinfunction "2_2") (pintype "passive"))
      (node (ref "R13") (pin "2") (pinfunction "2_2") (pintype "passive"))
      (node (ref "R14") (pin "2") (pinfunction "2_2") (pintype "passive"))
      (node (ref "U3") (pin "12") (pinfunction "VREG_12") (pintype "passive"))
    )
    (net (code "87") (name "YINPIN") (class "Default")
      (node (ref "C47") (pin "2") (pinfunction "2_2") (pintype "passive"))
      (node (ref "U2") (pin "125") (pinfunction "PG10/FSMC_NCE4_1/FSMC_NE3_125") (pintype "passive"))
    )
    (net (code "88") (name "YUNTAI") (class "Default")
      (node (ref "JP2") (pin "1") (pinfunction "1_1") (pintype "passive"))
      (node (ref "U2") (pin "22") (pinfunction "PF10/FSMC_INTR/ADC3_IN8_22") (pintype "passive"))
    )
    (net (code "89") (name "unconnected-(U1-CTS#-Pad9)") (class "Default")
      (node (ref "U1") (pin "9") (pinfunction "CTS#_9") (pintype "passive+no_connect"))
    )
    (net (code "90") (name "unconnected-(U1-DCD#-Pad12)") (class "Default")
      (node (ref "U1") (pin "12") (pinfunction "DCD#_12") (pintype "passive+no_connect"))
    )
    (net (code "91") (name "unconnected-(U1-DSR#-Pad10)") (class "Default")
      (node (ref "U1") (pin "10") (pinfunction "DSR#_10") (pintype "passive+no_connect"))
    )
    (net (code "92") (name "unconnected-(U1-RI#-Pad11)") (class "Default")
      (node (ref "U1") (pin "11") (pinfunction "RI#_11") (pintype "passive+no_connect"))
    )
    (net (code "93") (name "unconnected-(U1-RS232-Pad15)") (class "Default")
      (node (ref "U1") (pin "15") (pinfunction "RS232_15") (pintype "passive+no_connect"))
    )
    (net (code "94") (name "unconnected-(U2-PA0-WKUP{slash}U2_CTS{slash}U4_TX{slash}ETH_MII_CRS{slash}TIM2_CH1_ETR{slash}TIM5_CH1{slash}TIM8_ETR{slash}ADC123_IN0-Pad34)") (class "Default")
      (node (ref "U2") (pin "34") (pinfunction "PA0-WKUP/U2_CTS/U4_TX/ETH_MII_CRS/TIM2_CH1_ETR/TIM5_CH1/TIM8_ETR/ADC123_IN0_34") (pintype "passive"))
    )
    (net (code "95") (name "unconnected-(U2-PA1{slash}U2_RTS{slash}U4_RX{slash}ETH_RMII_REF_CLK{slash}ETH_MII_RX_CLK{slash}TIM2_CH2{slash}TIM5_CH2{slash}ADC123_IN1-Pad35)") (class "Default")
      (node (ref "U2") (pin "35") (pinfunction "PA1/U2_RTS/U4_RX/ETH_RMII_REF_CLK/ETH_MII_RX_CLK/TIM2_CH2/TIM5_CH2/ADC123_IN1_35") (pintype "passive"))
    )
    (net (code "96") (name "unconnected-(U2-PA8{slash}TIM1_CH1{slash}U1_CK{slash}I2C3_SCL{slash}MCO1{slash}OTG_FS_SOF-Pad100)") (class "Default")
      (node (ref "U2") (pin "100") (pinfunction "PA8/TIM1_CH1/U1_CK/I2C3_SCL/MCO1/OTG_FS_SOF_100") (pintype "passive"))
    )
    (net (code "97") (name "unconnected-(U2-PA11{slash}TIM1_CH4{slash}U1_CTS{slash}CAN1_RX{slash}OTG_FS_DM-Pad103)") (class "Default")
      (node (ref "U2") (pin "103") (pinfunction "PA11/TIM1_CH4/U1_CTS/CAN1_RX/OTG_FS_DM_103") (pintype "passive"))
    )
    (net (code "98") (name "unconnected-(U2-PA12{slash}TIM1_ETR{slash}U1_RTS{slash}CAN1_TX{slash}OTG_FS_DP-Pad104)") (class "Default")
      (node (ref "U2") (pin "104") (pinfunction "PA12/TIM1_ETR/U1_RTS/CAN1_TX/OTG_FS_DP_104") (pintype "passive"))
    )
    (net (code "99") (name "unconnected-(U2-PB3{slash}JTDO{slash}TRACESWO{slash}TIM2_CH2{slash}SPI1_SCK{slash}SPI3_SCK{slash}I2S3_CK-Pad133)") (class "Default")
      (node (ref "U2") (pin "133") (pinfunction "PB3/JTDO/TRACESWO/TIM2_CH2/SPI1_SCK/SPI3_SCK/I2S3_CK_133") (pintype "passive"))
    )
    (net (code "100") (name "unconnected-(U2-PB4{slash}JNTRST{slash}TIM3_CH1{slash}SPI1_MISO{slash}SPI3_MISO{slash}I2S3ext_SD-Pad134)") (class "Default")
      (node (ref "U2") (pin "134") (pinfunction "PB4/JNTRST/TIM3_CH1/SPI1_MISO/SPI3_MISO/I2S3ext_SD_134") (pintype "passive"))
    )
    (net (code "101") (name "unconnected-(U2-PB5{slash}TIM3_CH2{slash}SPI1_MOSI{slash}SPI3_MOSI{slash}CAN2_RX{slash}I2C1_SMBA{slash}OTG_HS_ULPI_D7{slash}ETH_PPS_OUT{slash}DCMI_D10{slash}I2S3_SD-Pad135)") (class "Default")
      (node (ref "U2") (pin "135") (pinfunction "PB5/TIM3_CH2/SPI1_MOSI/SPI3_MOSI/CAN2_RX/I2C1_SMBA/OTG_HS_ULPI_D7/ETH_PPS_OUT/DCMI_D10/I2S3_SD_135") (pintype "passive"))
    )
    (net (code "102") (name "unconnected-(U2-PB6{slash}TIM4_CH1{slash}U1_TX{slash}CAN2_TX{slash}I2C1_SCL{slash}DCMI_D5-Pad136)") (class "Default")
      (node (ref "U2") (pin "136") (pinfunction "PB6/TIM4_CH1/U1_TX/CAN2_TX/I2C1_SCL/DCMI_D5_136") (pintype "passive"))
    )
    (net (code "103") (name "unconnected-(U2-PB7{slash}TIM4_CH2{slash}U1_RX{slash}FSMC_NL{slash}I2C1_SDA{slash}DCMI_VSYNC-Pad137)") (class "Default")
      (node (ref "U2") (pin "137") (pinfunction "PB7/TIM4_CH2/U1_RX/FSMC_NL/I2C1_SDA/DCMI_VSYNC_137") (pintype "passive"))
    )
    (net (code "104") (name "unconnected-(U2-PB8{slash}TIM4_CH3{slash}TIM10_CH1{slash}CAN1_RX{slash}SDIO_D4{slash}ETH_MII_TXD3{slash}I2C1_SCL{slash}DCMI_D6-Pad139)") (class "Default")
      (node (ref "U2") (pin "139") (pinfunction "PB8/TIM4_CH3/TIM10_CH1/CAN1_RX/SDIO_D4/ETH_MII_TXD3/I2C1_SCL/DCMI_D6_139") (pintype "passive"))
    )
    (net (code "105") (name "unconnected-(U2-PB9{slash}TIM4_CH4{slash}TIM11_CH1{slash}CAN1_TX{slash}SDIO_D5{slash}SPI2_NSS{slash}I2C1_SDA{slash}DCMI_D7{slash}I2S2_WS-Pad140)") (class "Default")
      (node (ref "U2") (pin "140") (pinfunction "PB9/TIM4_CH4/TIM11_CH1/CAN1_TX/SDIO_D5/SPI2_NSS/I2C1_SDA/DCMI_D7/I2S2_WS_140") (pintype "passive"))
    )
    (net (code "106") (name "unconnected-(U2-PB10{slash}SPI2_SCK{slash}TIM2_CH3{slash}U3_TX{slash}I2C2_SCL{slash}OTG_HS_ULPI_D3{slash}I2S2_CK-Pad69)") (class "Default")
      (node (ref "U2") (pin "69") (pinfunction "PB10/SPI2_SCK/TIM2_CH3/U3_TX/I2C2_SCL/OTG_HS_ULPI_D3/I2S2_CK_69") (pintype "passive"))
    )
    (net (code "107") (name "unconnected-(U2-PB11{slash}TIM2_CH4{slash}U3_RX{slash}I2C2_SDA{slash}HS_ULPI_D4{slash}ETH_MII_TX_EN{slash}ETH_RMII_TX_EN-Pad70)") (class "Default")
      (node (ref "U2") (pin "70") (pinfunction "PB11/TIM2_CH4/U3_RX/I2C2_SDA/HS_ULPI_D4/ETH_MII_TX_EN/ETH_RMII_TX_EN_70") (pintype "passive"))
    )
    (net (code "108") (name "unconnected-(U2-PB12{slash}SPI2_NSS{slash}TIM1_BKIN{slash}U3_CK{slash}CAN2_RX{slash}I2C2_SMBA{slash}OTG_HS_ULPI_D5{slash}OTG_HS_ID{slash}ETH_MII_TXD0{slash}ETH_RMII_TXD0{slash}I2S2_WS-Pad73)") (class "Default")
      (node (ref "U2") (pin "73") (pinfunction "PB12/SPI2_NSS/TIM1_BKIN/U3_CK/CAN2_RX/I2C2_SMBA/OTG_HS_ULPI_D5/OTG_HS_ID/ETH_MII_TXD0/ETH_RMII_TXD0/I2S2_WS_73") (pintype "passive"))
    )
    (net (code "109") (name "unconnected-(U2-PC0{slash}OTG_HS_ULPI_STP{slash}ADC123_IN10-Pad26)") (class "Default")
      (node (ref "U2") (pin "26") (pinfunction "PC0/OTG_HS_ULPI_STP/ADC123_IN10_26") (pintype "passive"))
    )
    (net (code "110") (name "unconnected-(U2-PC1{slash}ETH_MDC{slash}ADC123_IN11-Pad27)") (class "Default")
      (node (ref "U2") (pin "27") (pinfunction "PC1/ETH_MDC/ADC123_IN11_27") (pintype "passive"))
    )
    (net (code "111") (name "unconnected-(U2-PC2{slash}SPI2_MISO{slash}OTG_HS_ULPI_DIR{slash}ETH_MII_TXD2{slash}I2S2ext_SD{slash}ADC123_IN12-Pad28)") (class "Default")
      (node (ref "U2") (pin "28") (pinfunction "PC2/SPI2_MISO/OTG_HS_ULPI_DIR/ETH_MII_TXD2/I2S2ext_SD/ADC123_IN12_28") (pintype "passive"))
    )
    (net (code "112") (name "unconnected-(U2-PC3{slash}SPI2_MOSI{slash}OTG_HS_ULPI_NXT{slash}ETH_MII_TX_CLK{slash}I2S2_SD{slash}ADC123_IN13-Pad29)") (class "Default")
      (node (ref "U2") (pin "29") (pinfunction "PC3/SPI2_MOSI/OTG_HS_ULPI_NXT/ETH_MII_TX_CLK/I2S2_SD/ADC123_IN13_29") (pintype "passive"))
    )
    (net (code "113") (name "unconnected-(U2-PC4{slash}ETH_MII_RXD0{slash}ETH_RMII_RXD0{slash}ADC12_IN14-Pad44)") (class "Default")
      (node (ref "U2") (pin "44") (pinfunction "PC4/ETH_MII_RXD0/ETH_RMII_RXD0/ADC12_IN14_44") (pintype "passive"))
    )
    (net (code "114") (name "unconnected-(U2-PC5{slash}ETH_MII_RXD1{slash}ETH_RMII_RXD1{slash}ADC12_IN15-Pad45)") (class "Default")
      (node (ref "U2") (pin "45") (pinfunction "PC5/ETH_MII_RXD1/ETH_RMII_RXD1/ADC12_IN15_45") (pintype "passive"))
    )
    (net (code "115") (name "unconnected-(U2-PC6{slash}TIM3_CH1{slash}TIM8_CH1{slash}U6_TX{slash}SDIO_D6{slash}DCMI_D0{slash}I2S2_MCK-Pad96)") (class "Default")
      (node (ref "U2") (pin "96") (pinfunction "PC6/TIM3_CH1/TIM8_CH1/U6_TX/SDIO_D6/DCMI_D0/I2S2_MCK_96") (pintype "passive"))
    )
    (net (code "116") (name "unconnected-(U2-PC7{slash}TIM3_CH2{slash}TIM8_CH2{slash}U6_RX{slash}SDIO_D7{slash}DCMI_D1{slash}I2S3_MCK-Pad97)") (class "Default")
      (node (ref "U2") (pin "97") (pinfunction "PC7/TIM3_CH2/TIM8_CH2/U6_RX/SDIO_D7/DCMI_D1/I2S3_MCK_97") (pintype "passive"))
    )
    (net (code "117") (name "unconnected-(U2-PC8{slash}TIM3_CH3{slash}TIM8_CH3{slash}U6_CK{slash}SDIO_D0{slash}DCMI_D2-Pad98)") (class "Default")
      (node (ref "U2") (pin "98") (pinfunction "PC8/TIM3_CH3/TIM8_CH3/U6_CK/SDIO_D0/DCMI_D2_98") (pintype "passive"))
    )
    (net (code "118") (name "unconnected-(U2-PC9{slash}TIM3_CH4{slash}TIM8_CH4{slash}I2C3_SDA{slash}SDIO_D1{slash}DCMI_D3{slash}MCO2{slash}I2S_CKIN-Pad99)") (class "Default")
      (node (ref "U2") (pin "99") (pinfunction "PC9/TIM3_CH4/TIM8_CH4/I2C3_SDA/SDIO_D1/DCMI_D3/MCO2/I2S_CKIN_99") (pintype "passive"))
    )
    (net (code "119") (name "unconnected-(U2-PC13{slash}RTC_AF1-Pad7)") (class "Default")
      (node (ref "U2") (pin "7") (pinfunction "PC13/RTC_AF1_7") (pintype "passive"))
    )
    (net (code "120") (name "unconnected-(U2-PD1{slash}FSMC_D3{slash}CAN1_TX-Pad115)") (class "Default")
      (node (ref "U2") (pin "115") (pinfunction "PD1/FSMC_D3/CAN1_TX_115") (pintype "passive"))
    )
    (net (code "121") (name "unconnected-(U2-PD2{slash}TIM3_ETR{slash}U5_RX{slash}SDIO_CMD{slash}DCMI_D11-Pad116)") (class "Default")
      (node (ref "U2") (pin "116") (pinfunction "PD2/TIM3_ETR/U5_RX/SDIO_CMD/DCMI_D11_116") (pintype "passive"))
    )
    (net (code "122") (name "unconnected-(U2-PD3{slash}FSMC_CLK{slash}U2_CTS-Pad117)") (class "Default")
      (node (ref "U2") (pin "117") (pinfunction "PD3/FSMC_CLK/U2_CTS_117") (pintype "passive"))
    )
    (net (code "123") (name "unconnected-(U2-PD4{slash}FSMC_NOE{slash}U2_RTS-Pad118)") (class "Default")
      (node (ref "U2") (pin "118") (pinfunction "PD4/FSMC_NOE/U2_RTS_118") (pintype "passive"))
    )
    (net (code "124") (name "unconnected-(U2-PD5{slash}FSMC_NWE{slash}U2_TX-Pad119)") (class "Default")
      (node (ref "U2") (pin "119") (pinfunction "PD5/FSMC_NWE/U2_TX_119") (pintype "passive"))
    )
    (net (code "125") (name "unconnected-(U2-PD6{slash}FSMC_NWAIT{slash}U2_RX-Pad122)") (class "Default")
      (node (ref "U2") (pin "122") (pinfunction "PD6/FSMC_NWAIT/U2_RX_122") (pintype "passive"))
    )
    (net (code "126") (name "unconnected-(U2-PD7{slash}FSMC_NE1{slash}FSMC_NCE2{slash}U2_CK-Pad123)") (class "Default")
      (node (ref "U2") (pin "123") (pinfunction "PD7/FSMC_NE1/FSMC_NCE2/U2_CK_123") (pintype "passive"))
    )
    (net (code "127") (name "unconnected-(U2-PD14{slash}FSMC_D0{slash}TIM4_CH3-Pad85)") (class "Default")
      (node (ref "U2") (pin "85") (pinfunction "PD14/FSMC_D0/TIM4_CH3_85") (pintype "passive"))
    )
    (net (code "128") (name "unconnected-(U2-PD15{slash}FSMC_D1{slash}TIM4_CH4-Pad86)") (class "Default")
      (node (ref "U2") (pin "86") (pinfunction "PD15/FSMC_D1/TIM4_CH4_86") (pintype "passive"))
    )
    (net (code "129") (name "unconnected-(U2-PE0{slash}TIM4_ETR{slash}FSMC_NBL0{slash}DCMI_D2-Pad141)") (class "Default")
      (node (ref "U2") (pin "141") (pinfunction "PE0/TIM4_ETR/FSMC_NBL0/DCMI_D2_141") (pintype "passive"))
    )
    (net (code "130") (name "unconnected-(U2-PE1{slash}FSMC_NBL1{slash}DCMI_D3-Pad142)") (class "Default")
      (node (ref "U2") (pin "142") (pinfunction "PE1/FSMC_NBL1/DCMI_D3_142") (pintype "passive"))
    )
    (net (code "131") (name "unconnected-(U2-PE5{slash}TRACED2{slash}FSMC_A21{slash}TIM9_CH1{slash}DCMI_D6-Pad4)") (class "Default")
      (node (ref "U2") (pin "4") (pinfunction "PE5/TRACED2/FSMC_A21/TIM9_CH1/DCMI_D6_4") (pintype "passive"))
    )
    (net (code "132") (name "unconnected-(U2-PE6{slash}TRACED3{slash}FSMC_A22{slash}TIM9_CH2{slash}DCMI_D7-Pad5)") (class "Default")
      (node (ref "U2") (pin "5") (pinfunction "PE6/TRACED3/FSMC_A22/TIM9_CH2/DCMI_D7_5") (pintype "passive"))
    )
    (net (code "133") (name "unconnected-(U2-PE7{slash}FSMC_D4{slash}TIM1_ETR-Pad58)") (class "Default")
      (node (ref "U2") (pin "58") (pinfunction "PE7/FSMC_D4/TIM1_ETR_58") (pintype "passive"))
    )
    (net (code "134") (name "unconnected-(U2-PE8{slash}FSMC_D5{slash}TIM1_CH1N-Pad59)") (class "Default")
      (node (ref "U2") (pin "59") (pinfunction "PE8/FSMC_D5/TIM1_CH1N_59") (pintype "passive"))
    )
    (net (code "135") (name "unconnected-(U2-PE9{slash}FSMC_D6{slash}TIM1_CH1-Pad60)") (class "Default")
      (node (ref "U2") (pin "60") (pinfunction "PE9/FSMC_D6/TIM1_CH1_60") (pintype "passive"))
    )
    (net (code "136") (name "unconnected-(U2-PE10{slash}FSMC_D7{slash}TIM1_CH2N-Pad63)") (class "Default")
      (node (ref "U2") (pin "63") (pinfunction "PE10/FSMC_D7/TIM1_CH2N_63") (pintype "passive"))
    )
    (net (code "137") (name "unconnected-(U2-PE11{slash}FSMC_D8{slash}TIM1_CH2-Pad64)") (class "Default")
      (node (ref "U2") (pin "64") (pinfunction "PE11/FSMC_D8/TIM1_CH2_64") (pintype "passive"))
    )
    (net (code "138") (name "unconnected-(U2-PE12{slash}FSMC_D9{slash}TIM1_CH3N-Pad65)") (class "Default")
      (node (ref "U2") (pin "65") (pinfunction "PE12/FSMC_D9/TIM1_CH3N_65") (pintype "passive"))
    )
    (net (code "139") (name "unconnected-(U2-PE13{slash}FSMC_D10{slash}TIM1_CH3-Pad66)") (class "Default")
      (node (ref "U2") (pin "66") (pinfunction "PE13/FSMC_D10/TIM1_CH3_66") (pintype "passive"))
    )
    (net (code "140") (name "unconnected-(U2-PE14{slash}FSMC_D11{slash}TIM1_CH4-Pad67)") (class "Default")
      (node (ref "U2") (pin "67") (pinfunction "PE14/FSMC_D11/TIM1_CH4_67") (pintype "passive"))
    )
    (net (code "141") (name "unconnected-(U2-PE15{slash}FSMC_D12{slash}TIM1_BKIN-Pad68)") (class "Default")
      (node (ref "U2") (pin "68") (pinfunction "PE15/FSMC_D12/TIM1_BKIN_68") (pintype "passive"))
    )
    (net (code "142") (name "unconnected-(U2-PF11{slash}DCMI_D12-Pad49)") (class "Default")
      (node (ref "U2") (pin "49") (pinfunction "PF11/DCMI_D12_49") (pintype "passive"))
    )
    (net (code "143") (name "unconnected-(U2-PF12{slash}FSMC_A6-Pad50)") (class "Default")
      (node (ref "U2") (pin "50") (pinfunction "PF12/FSMC_A6_50") (pintype "passive"))
    )
    (net (code "144") (name "unconnected-(U2-PF13{slash}FSMC_A7-Pad53)") (class "Default")
      (node (ref "U2") (pin "53") (pinfunction "PF13/FSMC_A7_53") (pintype "passive"))
    )
    (net (code "145") (name "unconnected-(U2-PF14{slash}FSMC_A8-Pad54)") (class "Default")
      (node (ref "U2") (pin "54") (pinfunction "PF14/FSMC_A8_54") (pintype "passive"))
    )
    (net (code "146") (name "unconnected-(U2-PF15{slash}FSMC_A9-Pad55)") (class "Default")
      (node (ref "U2") (pin "55") (pinfunction "PF15/FSMC_A9_55") (pintype "passive"))
    )
    (net (code "147") (name "unconnected-(U2-PG0{slash}FSMC_A10-Pad56)") (class "Default")
      (node (ref "U2") (pin "56") (pinfunction "PG0/FSMC_A10_56") (pintype "passive"))
    )
    (net (code "148") (name "unconnected-(U2-PG1{slash}FSMC_A11-Pad57)") (class "Default")
      (node (ref "U2") (pin "57") (pinfunction "PG1/FSMC_A11_57") (pintype "passive"))
    )
    (net (code "149") (name "unconnected-(U2-PG2{slash}FSMC_A12-Pad87)") (class "Default")
      (node (ref "U2") (pin "87") (pinfunction "PG2/FSMC_A12_87") (pintype "passive"))
    )
    (net (code "150") (name "unconnected-(U2-PG3{slash}FSMC_A13-Pad88)") (class "Default")
      (node (ref "U2") (pin "88") (pinfunction "PG3/FSMC_A13_88") (pintype "passive"))
    )
    (net (code "151") (name "unconnected-(U2-PG4{slash}FSMC_A14-Pad89)") (class "Default")
      (node (ref "U2") (pin "89") (pinfunction "PG4/FSMC_A14_89") (pintype "passive"))
    )
    (net (code "152") (name "unconnected-(U2-PG5{slash}FSMC_A15-Pad90)") (class "Default")
      (node (ref "U2") (pin "90") (pinfunction "PG5/FSMC_A15_90") (pintype "passive"))
    )
    (net (code "153") (name "unconnected-(U2-PG6{slash}FSMC_INT2-Pad91)") (class "Default")
      (node (ref "U2") (pin "91") (pinfunction "PG6/FSMC_INT2_91") (pintype "passive"))
    )
    (net (code "154") (name "unconnected-(U2-PG7{slash}FSMC_INT3{slash}U6_CK-Pad92)") (class "Default")
      (node (ref "U2") (pin "92") (pinfunction "PG7/FSMC_INT3/U6_CK_92") (pintype "passive"))
    )
    (net (code "155") (name "unconnected-(U2-PG8{slash}U6_RTS{slash}ETH_PPS_OUT-Pad93)") (class "Default")
      (node (ref "U2") (pin "93") (pinfunction "PG8/U6_RTS/ETH_PPS_OUT_93") (pintype "passive"))
    )
    (net (code "156") (name "unconnected-(U2-PG9{slash}FSMC_NE2{slash}FSMC_NCE3{slash}U6_RX-Pad124)") (class "Default")
      (node (ref "U2") (pin "124") (pinfunction "PG9/FSMC_NE2/FSMC_NCE3/U6_RX_124") (pintype "passive"))
    )
    (net (code "157") (name "unconnected-(U2-PG12{slash}FSMC_NE4{slash}U6_RTS-Pad127)") (class "Default")
      (node (ref "U2") (pin "127") (pinfunction "PG12/FSMC_NE4/U6_RTS_127") (pintype "passive"))
    )
    (net (code "158") (name "unconnected-(U2-PG13{slash}FSMC_A24{slash}U6_CTS{slash}ETH_MII_TXD0{slash}ETH_RMII_TXD0-Pad128)") (class "Default")
      (node (ref "U2") (pin "128") (pinfunction "PG13/FSMC_A24/U6_CTS/ETH_MII_TXD0/ETH_RMII_TXD0_128") (pintype "passive"))
    )
    (net (code "159") (name "unconnected-(U3-L3-IRQ-Pad11)") (class "Default")
      (node (ref "U3") (pin "11") (pinfunction "L3-IRQ_11") (pintype "passive"))
    )
    (net (code "160") (name "unconnected-(U3-L4-Pad13)") (class "Default")
      (node (ref "U3") (pin "13") (pinfunction "L4_13") (pintype "passive"))
    )
    (net (code "161") (name "unconnected-(USB1-ID-Pad4)") (class "Default")
      (node (ref "USB1") (pin "4") (pinfunction "ID_4") (pintype "passive+no_connect"))
    )
  )
)
